# OB1_sensor_manufactured.net
KiCad netlist of a schematic drawn in EAGLE
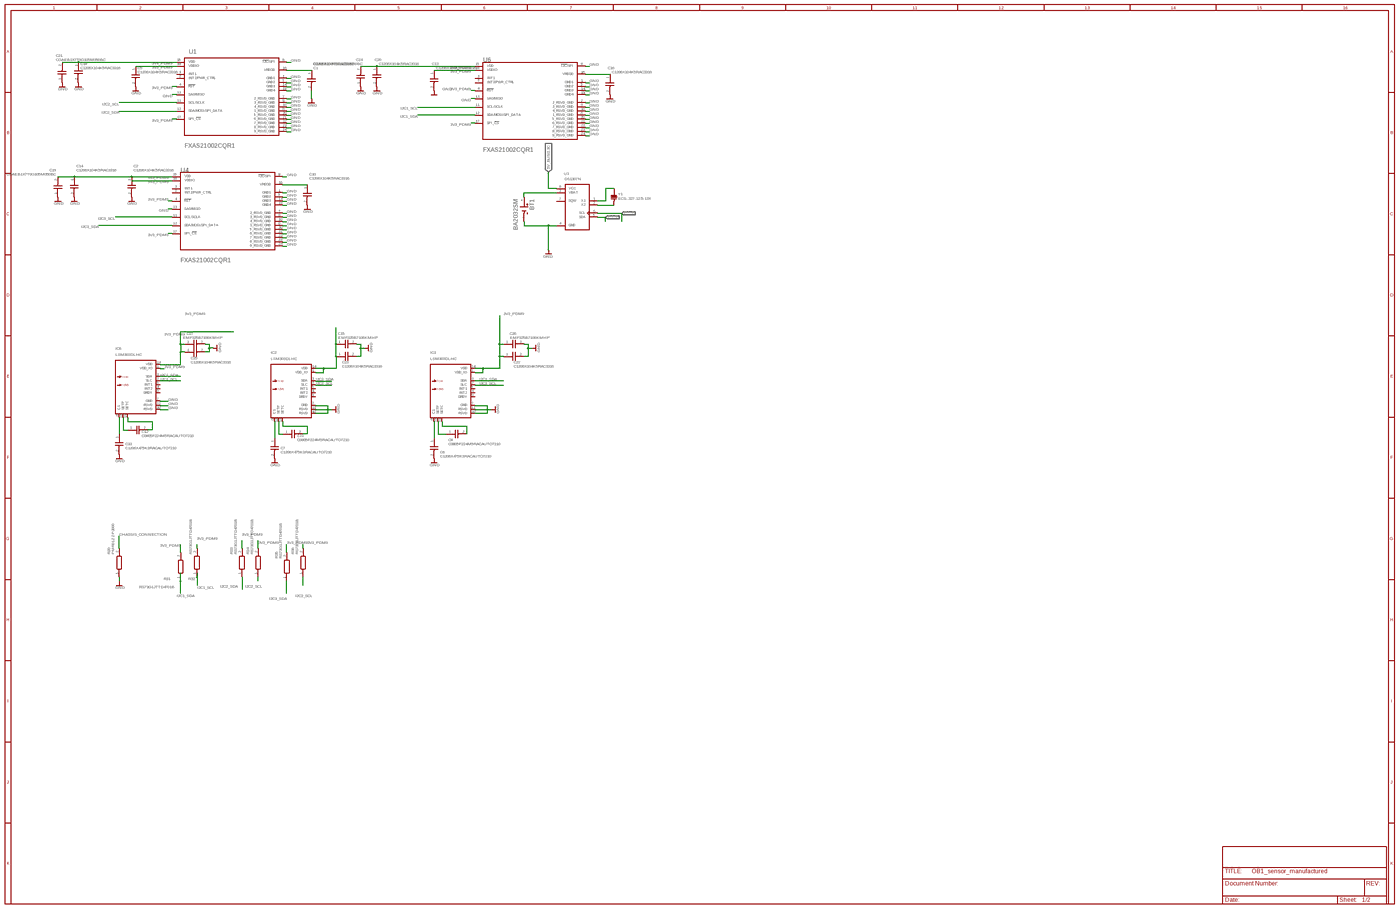
[diagram p0: schematic, sheet 1, overview]
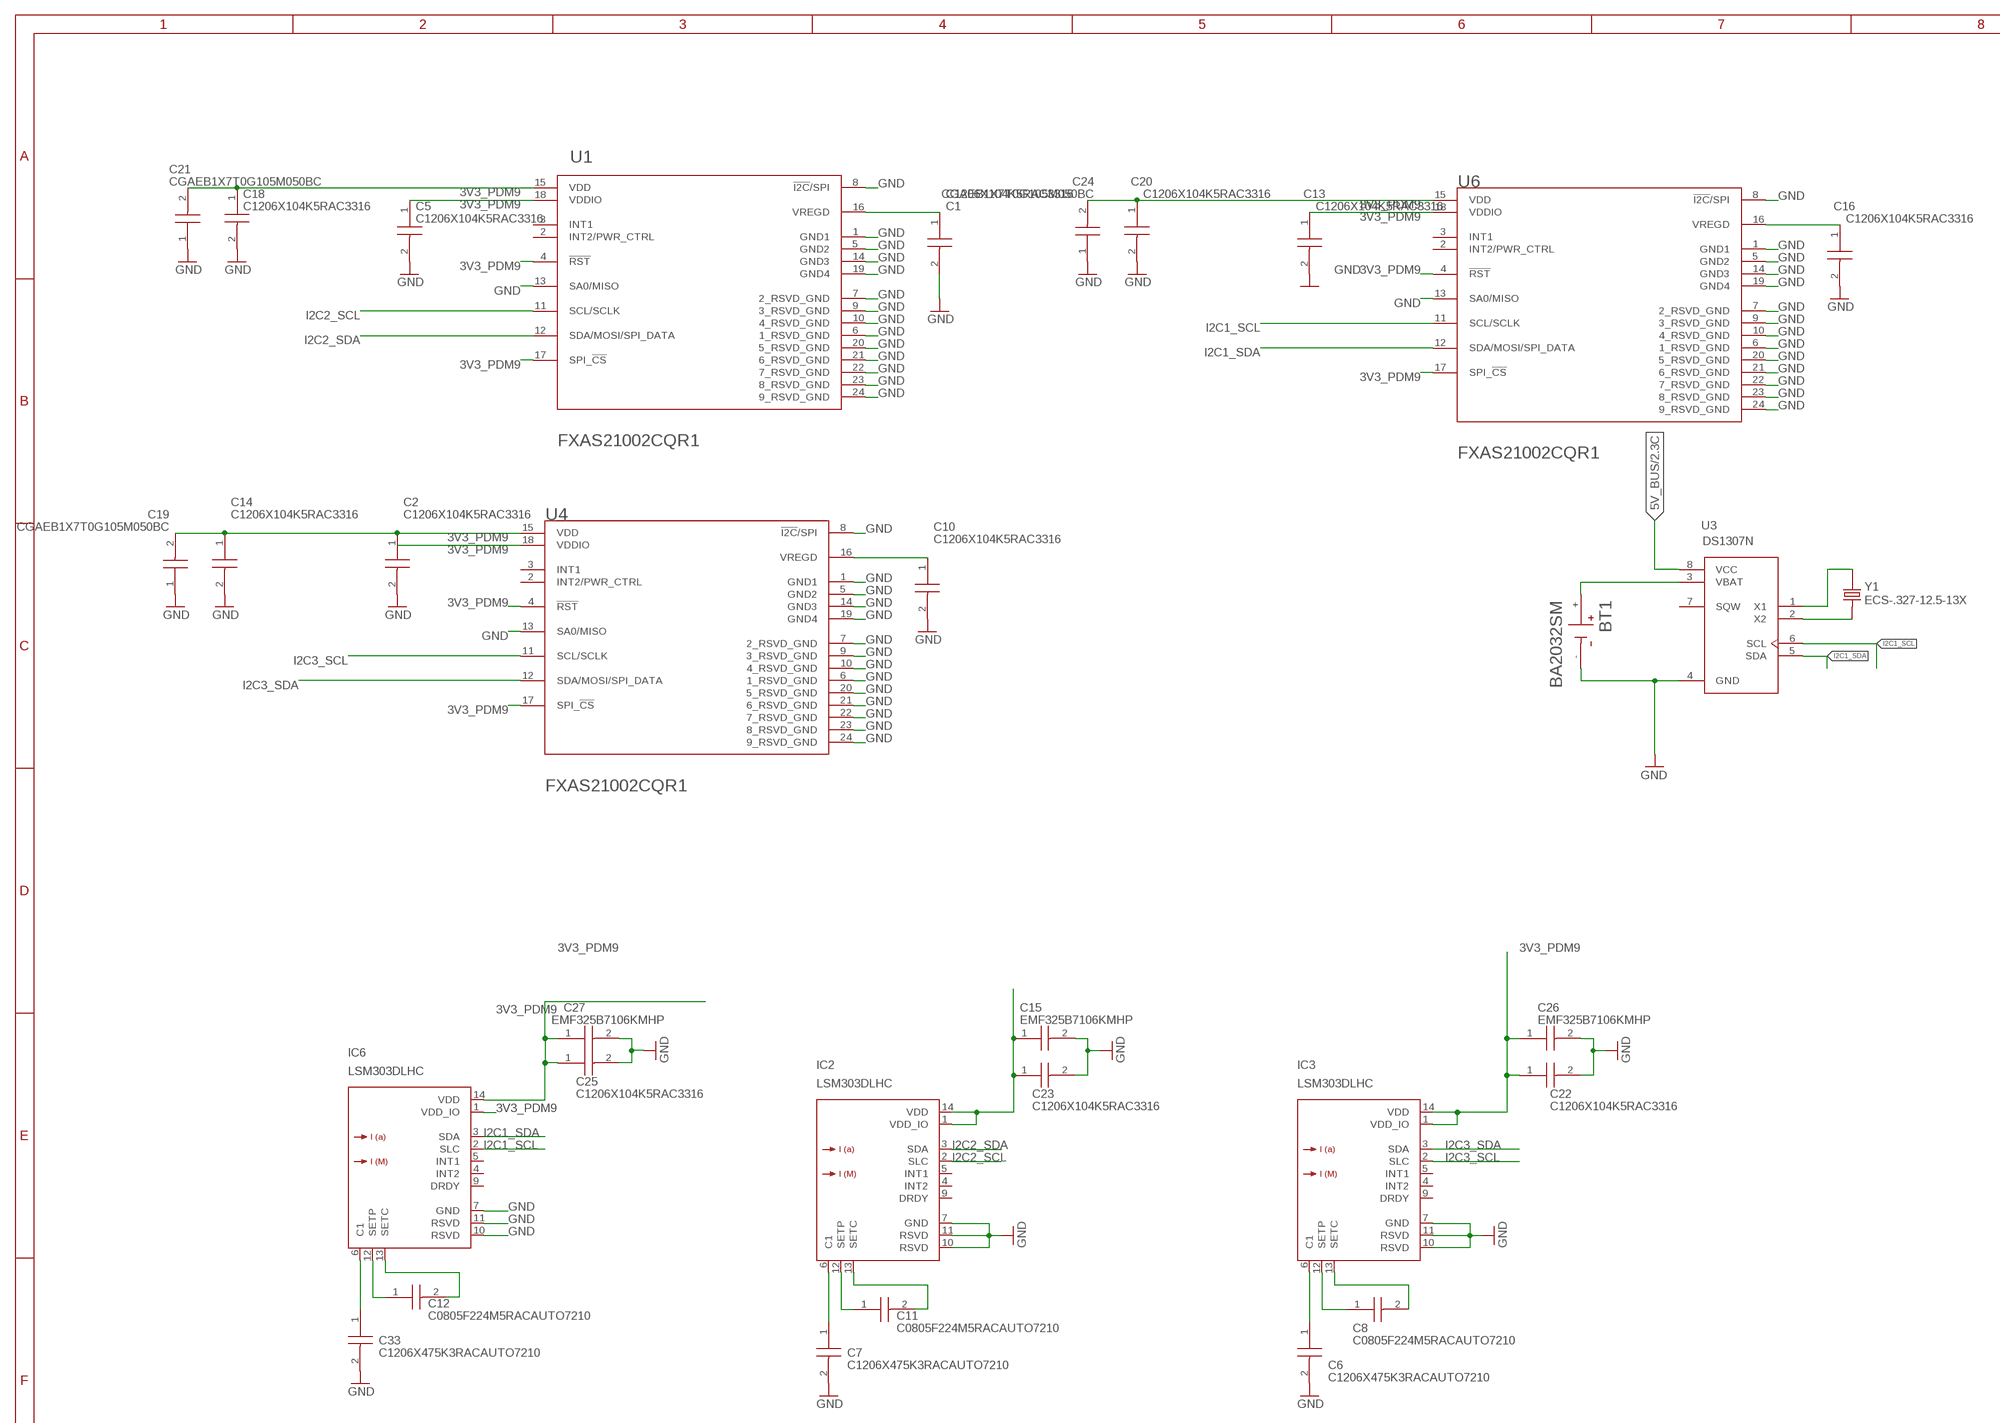
[diagram p1: schematic, sheet 1, part 1 of 4]
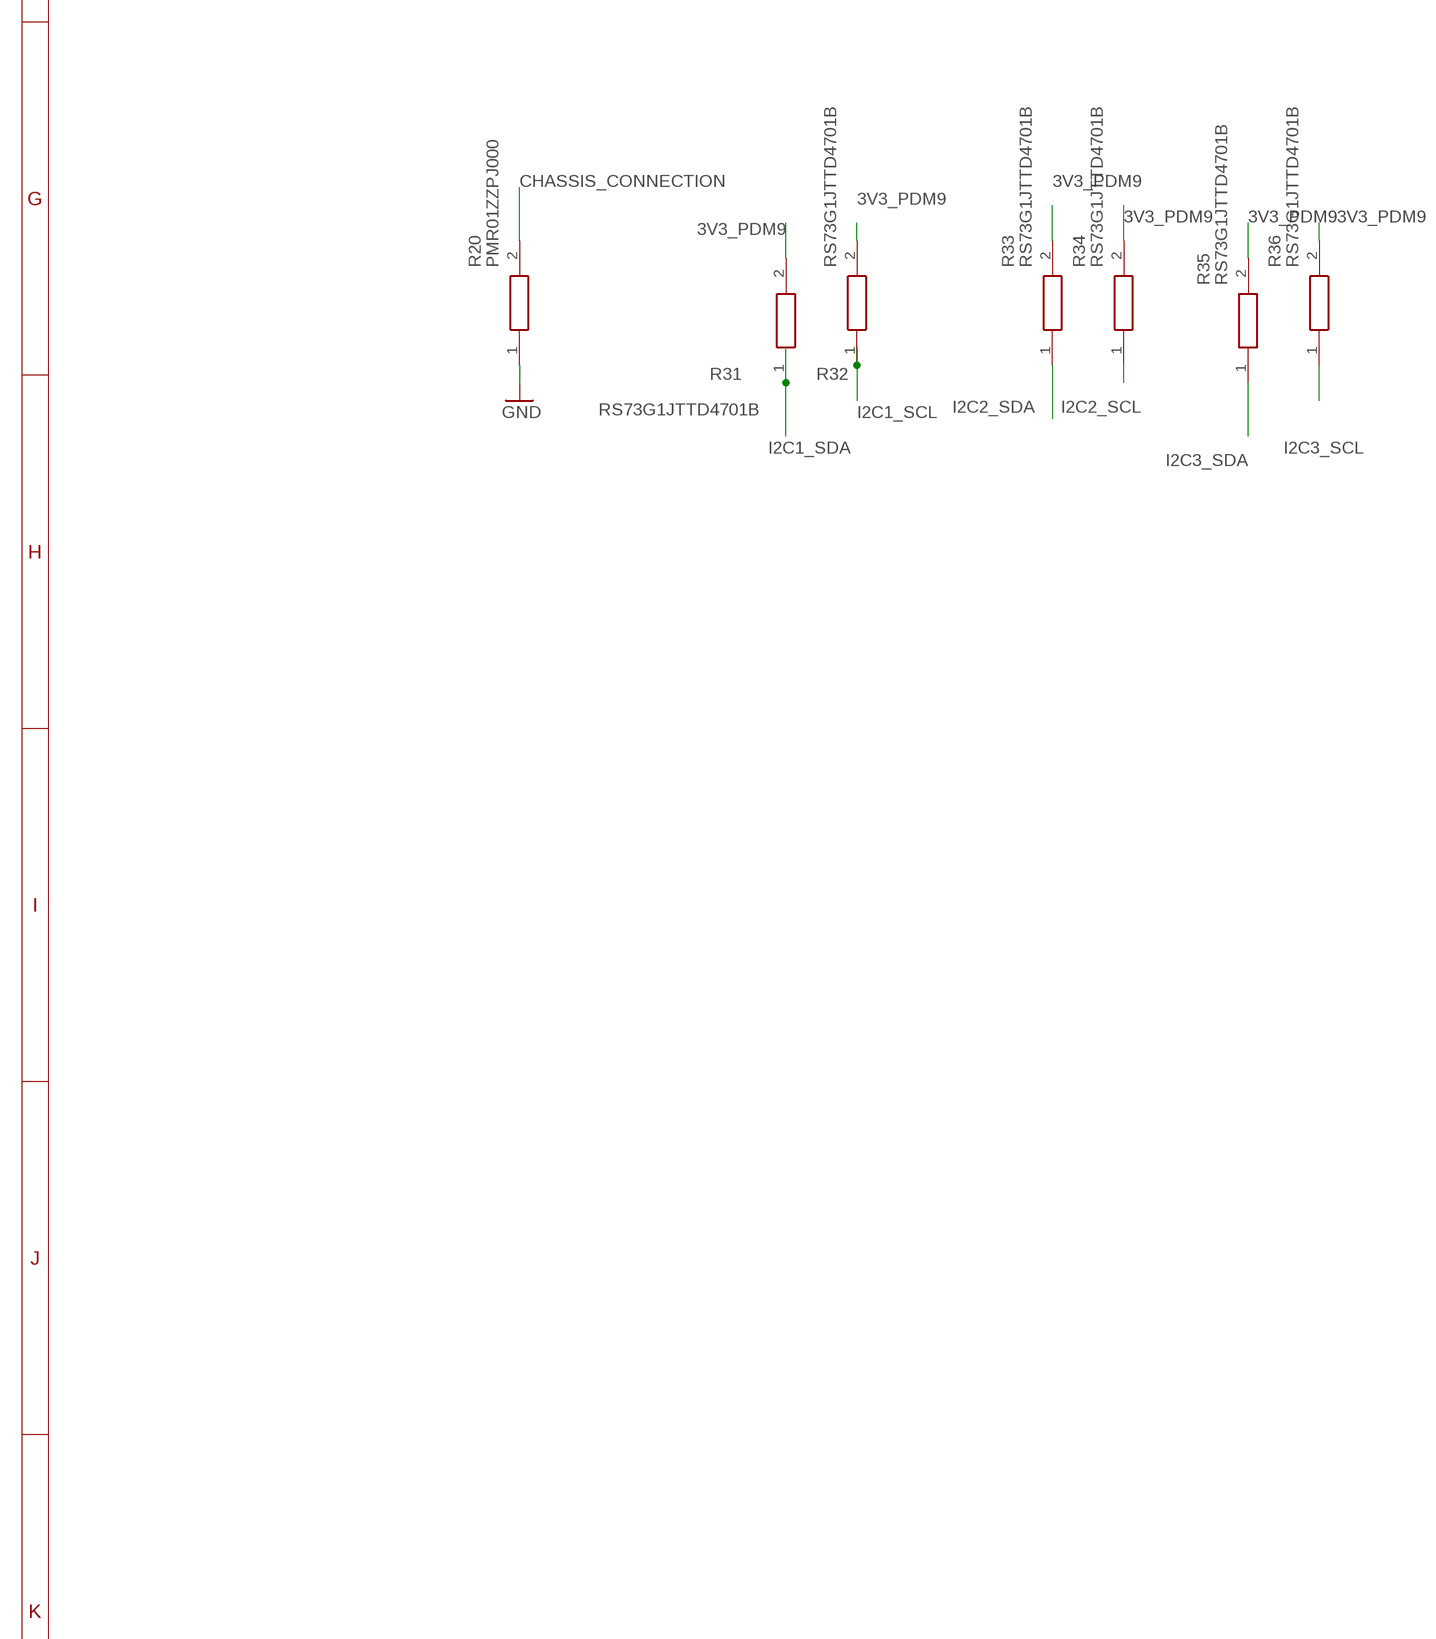
[diagram p2: schematic, sheet 1, part 2 of 4]
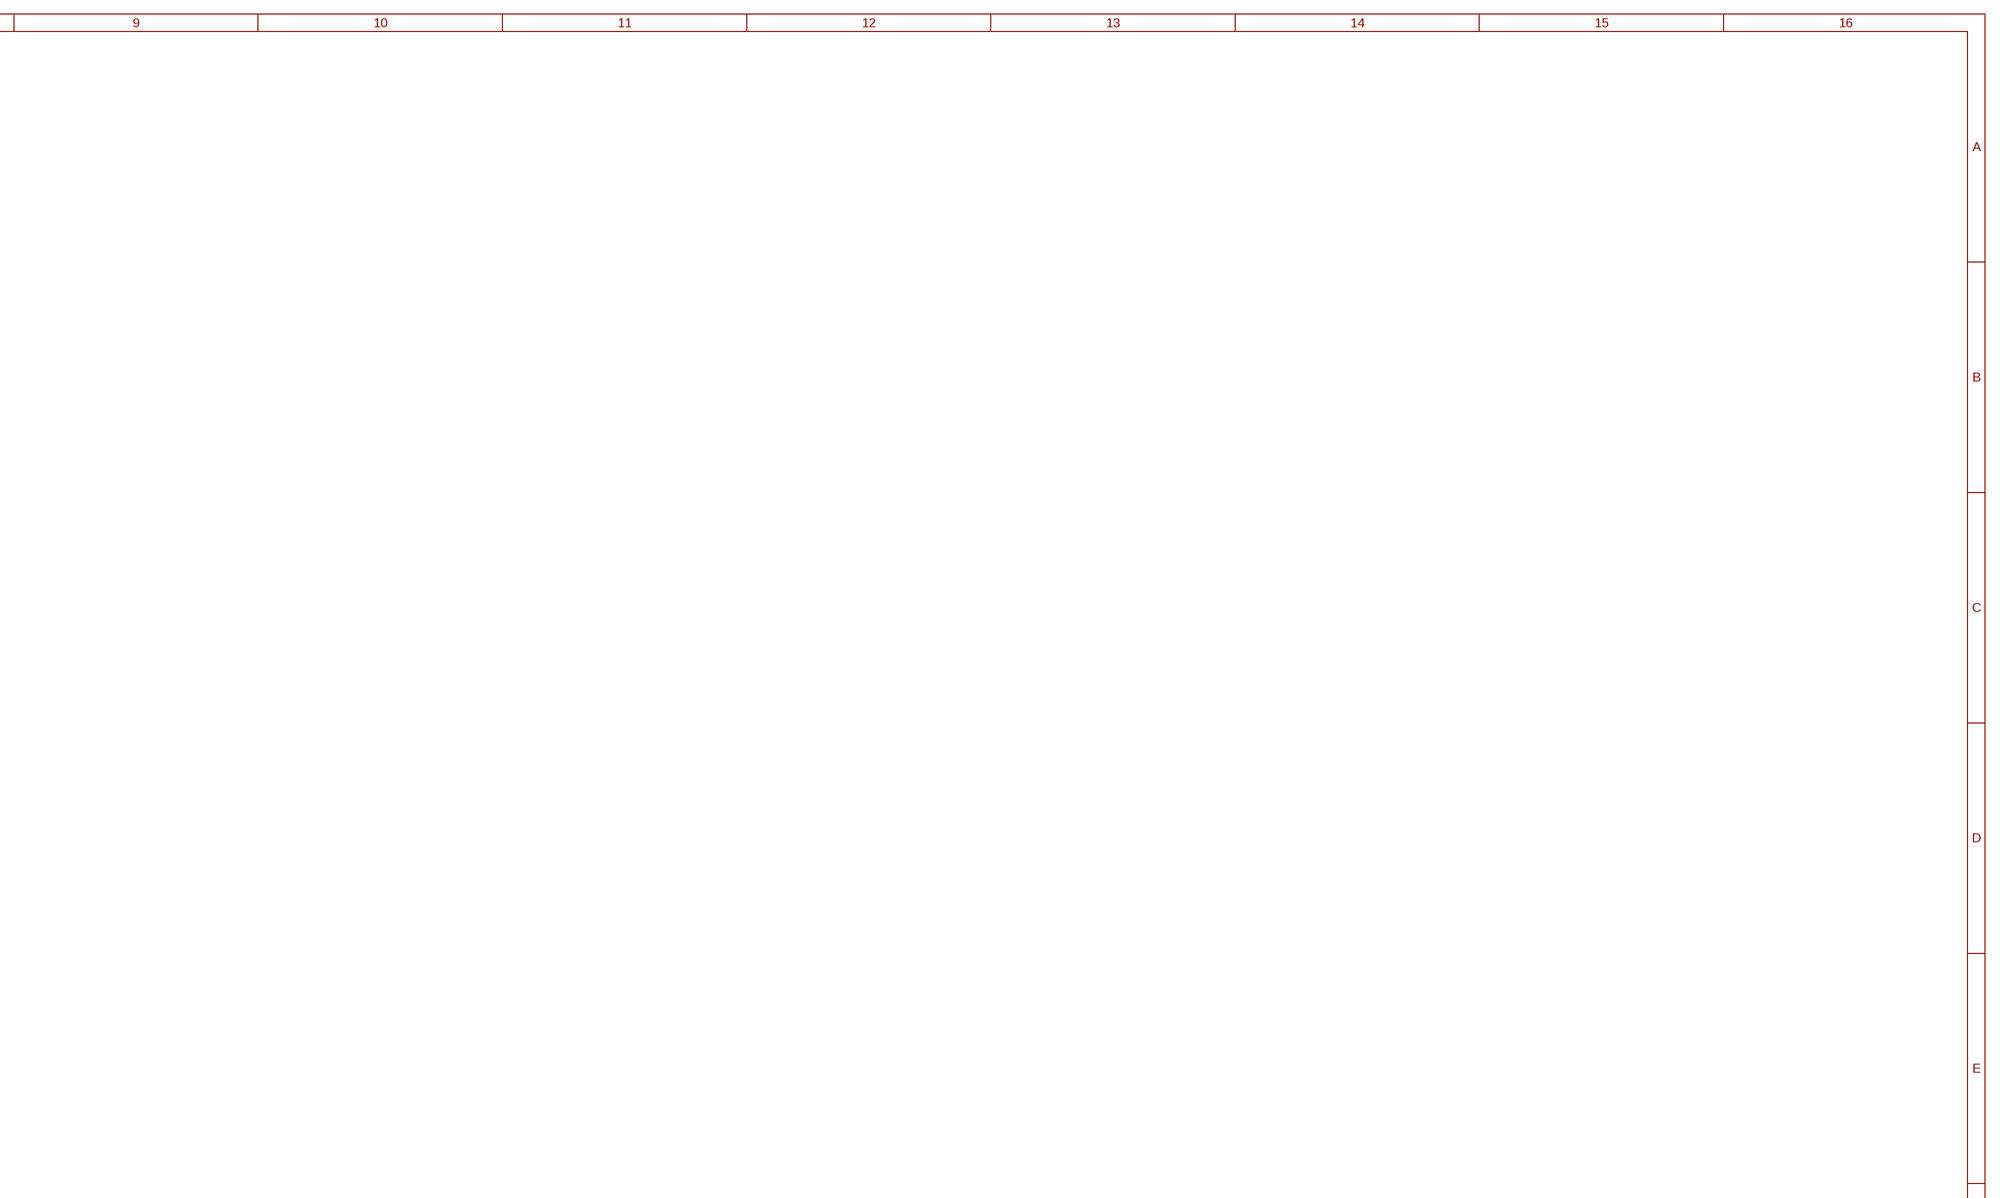
[diagram p3: schematic, sheet 1, part 3 of 4]
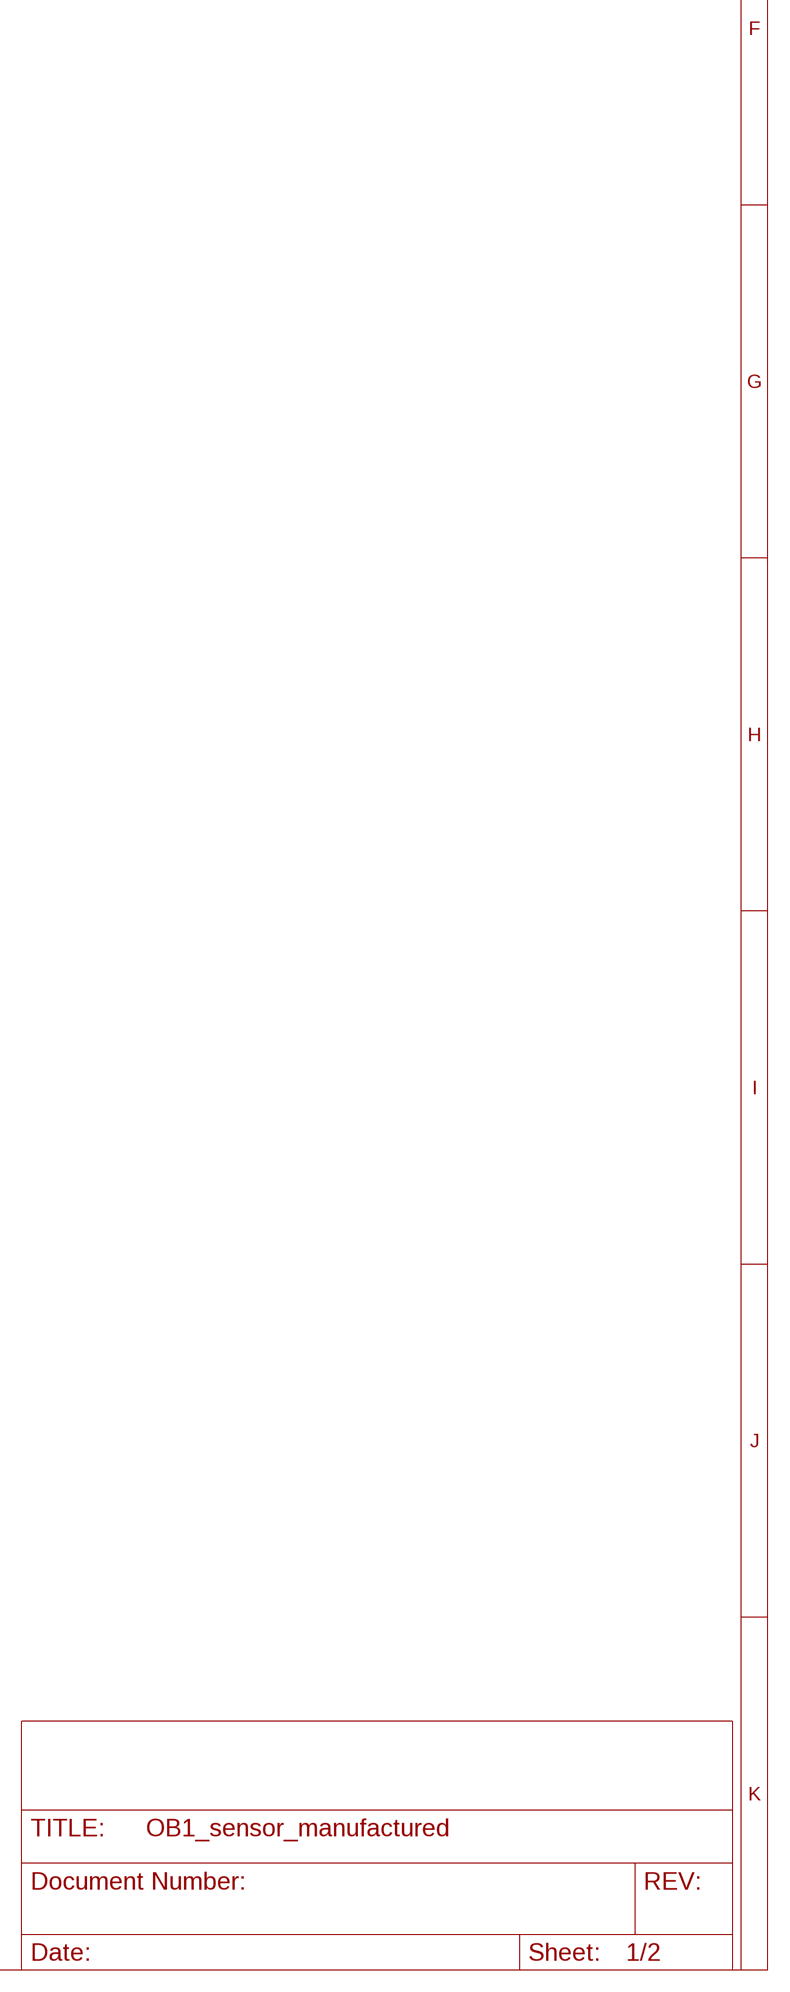
[diagram p4: schematic, sheet 1, part 4 of 4]
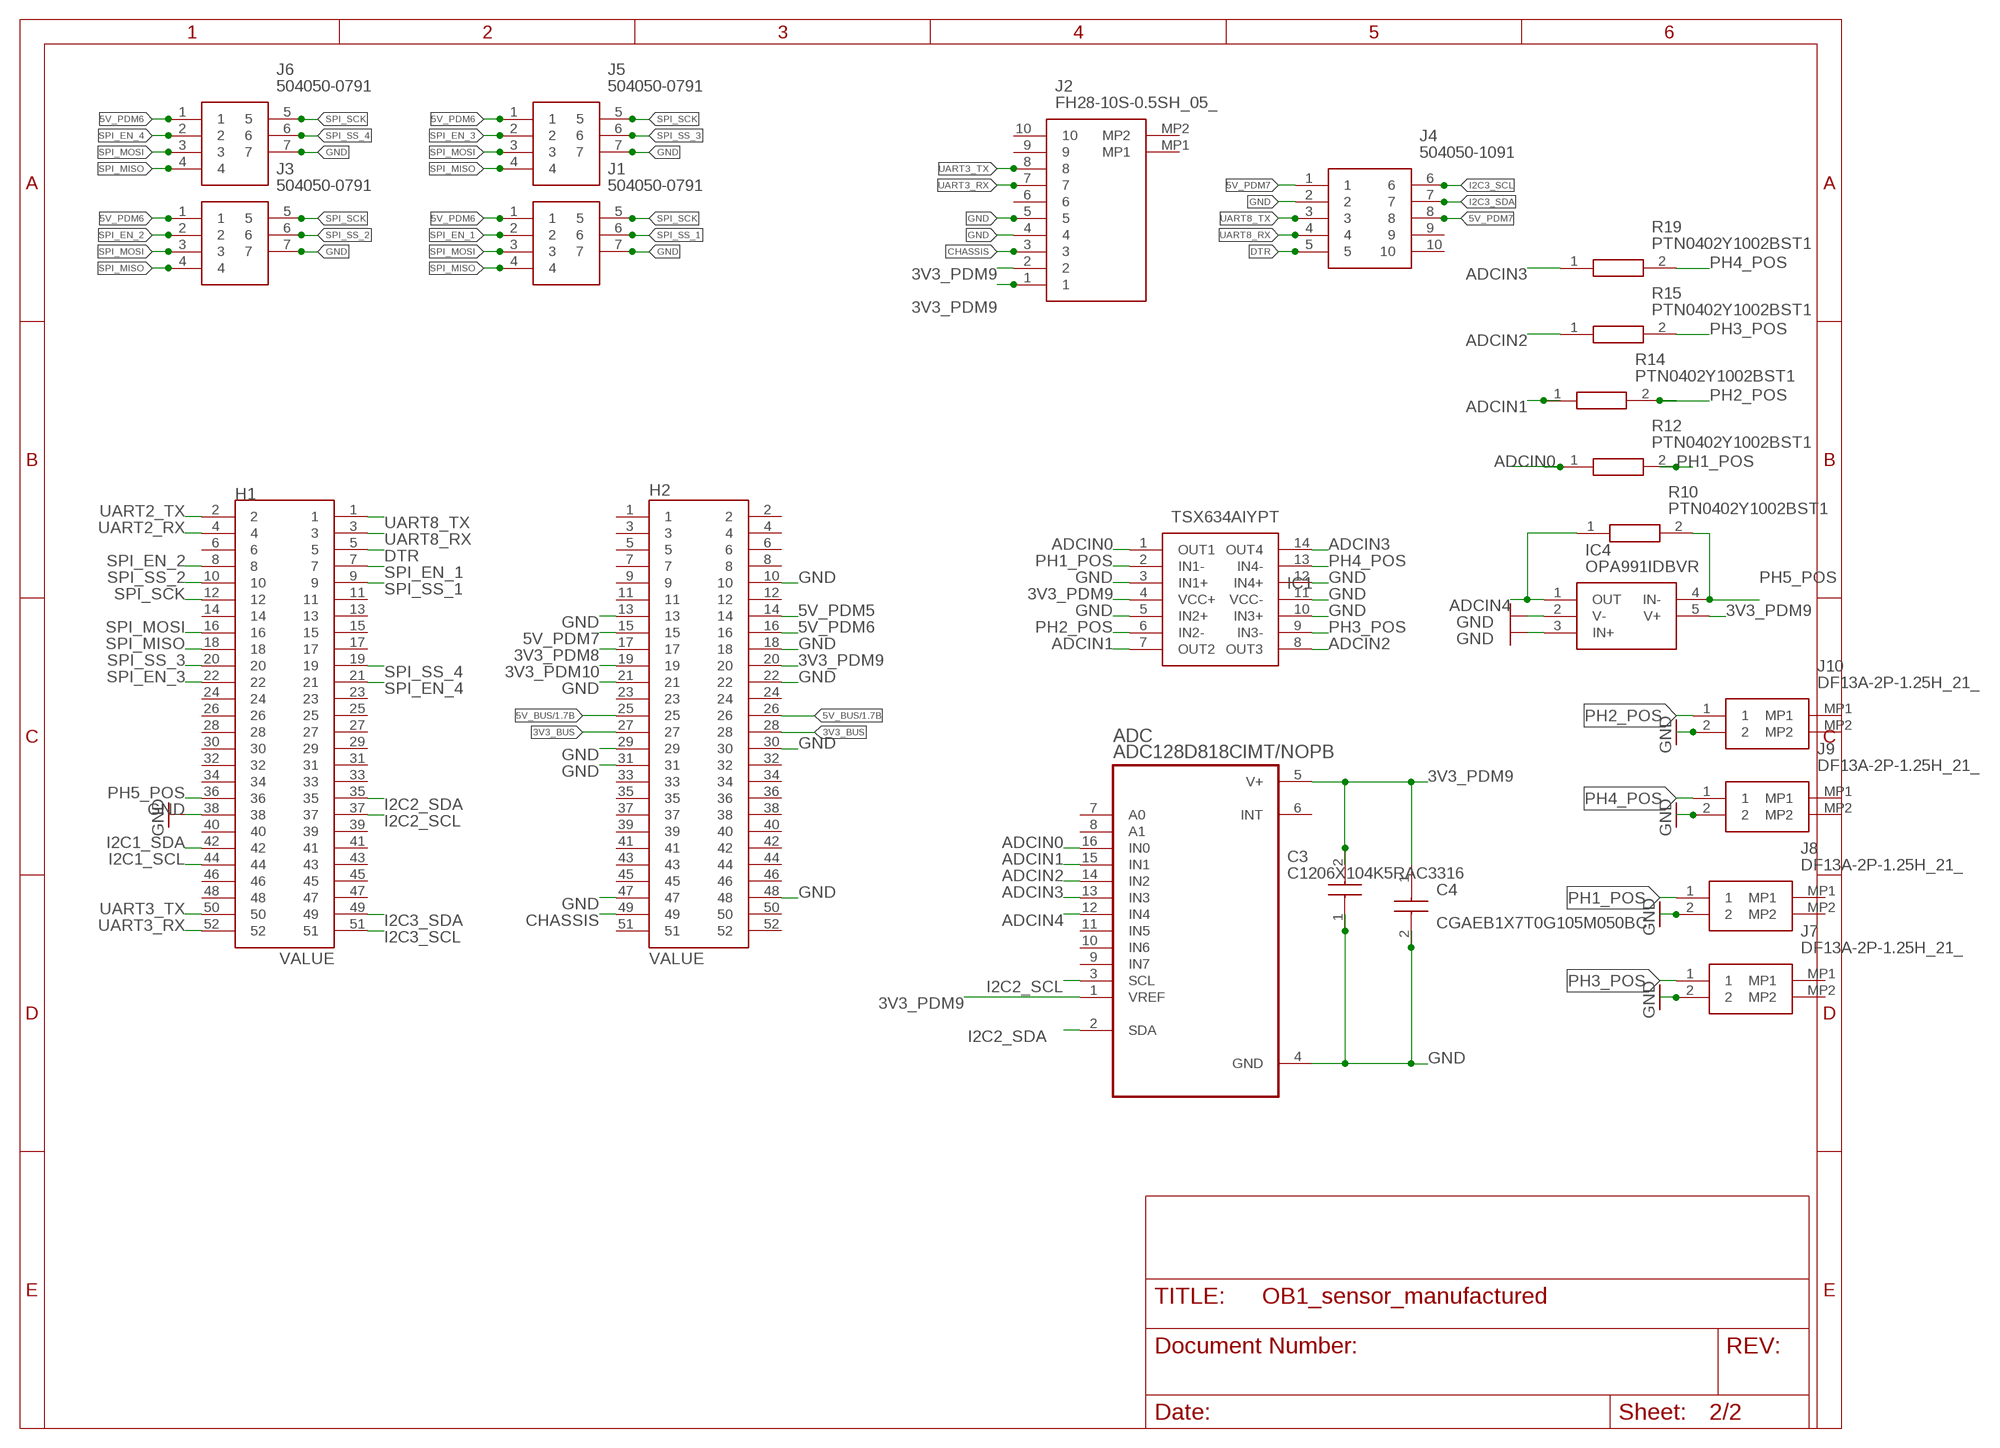
[diagram p5: schematic, sheet 2]

(export (version "E")
  (design (tool "Eeschema 10.0.6"))
  (components
    (comp (ref "BT1")
      (value "BA2032SM")
      (footprint "eagle-import:BAT_BA2032SM")
      (fields (field (name "DIGI-KEY_PART_NUMBER") "BA2032SM-ND") (field (name "MF") "MPD"))
      (libsource (lib "eagle-import") (part "BA2032SM"))
    )
    (comp (ref "C1")
      (value "C1206X104K5RAC3316")
      (footprint "eagle-import:CAPC3316X98N")
      (fields (field (name "MOUSER_PART_NUMBER") "80-C1206X104K5RC3316"))
      (libsource (lib "eagle-import") (part "C1206X104K5RAC3316"))
    )
    (comp (ref "C2")
      (value "C1206X104K5RAC3316")
      (footprint "eagle-import:CAPC3316X98N")
      (fields (field (name "MOUSER_PART_NUMBER") "80-C1206X104K5RC3316"))
      (libsource (lib "eagle-import") (part "C1206X104K5RAC3316"))
    )
    (comp (ref "C5")
      (value "C1206X104K5RAC3316")
      (footprint "eagle-import:CAPC3316X98N")
      (fields (field (name "MOUSER_PART_NUMBER") "80-C1206X104K5RC3316"))
      (libsource (lib "eagle-import") (part "C1206X104K5RAC3316"))
    )
    (comp (ref "C6")
      (value "C1206X475K3RACAUTO7210")
      (footprint "eagle-import:CAPC3316X195N")
      (fields (field (name "MOUSER_PART_NUMBER") "80-C1206X475K3RAUTLR"))
      (libsource (lib "eagle-import") (part "C1206X475K3RACAUTO7210"))
    )
    (comp (ref "C7")
      (value "C1206X475K3RACAUTO7210")
      (footprint "eagle-import:CAPC3316X195N")
      (fields (field (name "MOUSER_PART_NUMBER") "80-C1206X475K3RAUTLR"))
      (libsource (lib "eagle-import") (part "C1206X475K3RACAUTO7210"))
    )
    (comp (ref "C8")
      (value "C0805F224M5RACAUTO7210")
      (footprint "eagle-import:CAPC2012X140N")
      (fields (field (name "MOUSER_PART_NUMBER") "80-C0805F224M5RAUTLR"))
      (libsource (lib "eagle-import") (part "C0805F224M5RACAUTO7210"))
    )
    (comp (ref "C10")
      (value "C1206X104K5RAC3316")
      (footprint "eagle-import:CAPC3316X98N")
      (fields (field (name "MOUSER_PART_NUMBER") "80-C1206X104K5RC3316"))
      (libsource (lib "eagle-import") (part "C1206X104K5RAC3316"))
    )
    (comp (ref "C11")
      (value "C0805F224M5RACAUTO7210")
      (footprint "eagle-import:CAPC2012X140N")
      (fields (field (name "MOUSER_PART_NUMBER") "80-C0805F224M5RAUTLR"))
      (libsource (lib "eagle-import") (part "C0805F224M5RACAUTO7210"))
    )
    (comp (ref "C12")
      (value "C0805F224M5RACAUTO7210")
      (footprint "eagle-import:CAPC2012X140N")
      (fields (field (name "MOUSER_PART_NUMBER") "80-C0805F224M5RAUTLR"))
      (libsource (lib "eagle-import") (part "C0805F224M5RACAUTO7210"))
    )
    (comp (ref "C13")
      (value "C1206X104K5RAC3316")
      (footprint "eagle-import:CAPC3316X98N")
      (fields (field (name "MOUSER_PART_NUMBER") "80-C1206X104K5RC3316"))
      (libsource (lib "eagle-import") (part "C1206X104K5RAC3316"))
    )
    (comp (ref "C14")
      (value "C1206X104K5RAC3316")
      (footprint "eagle-import:CAPC3316X98N")
      (fields (field (name "MOUSER_PART_NUMBER") "80-C1206X104K5RC3316"))
      (libsource (lib "eagle-import") (part "C1206X104K5RAC3316"))
    )
    (comp (ref "C15")
      (value "EMF325B7106KMHP")
      (footprint "eagle-import:CAPC3225X270N")
      (fields (field (name "MOUSER_PART_NUMBER") "963-EMF325B7106KMHP"))
      (libsource (lib "eagle-import") (part "EMF325B7106KMHP"))
    )
    (comp (ref "C16")
      (value "C1206X104K5RAC3316")
      (footprint "eagle-import:CAPC3316X98N")
      (fields (field (name "MOUSER_PART_NUMBER") "80-C1206X104K5RC3316"))
      (libsource (lib "eagle-import") (part "C1206X104K5RAC3316"))
    )
    (comp (ref "C18")
      (value "C1206X104K5RAC3316")
      (footprint "eagle-import:CAPC3316X98N")
      (fields (field (name "MOUSER_PART_NUMBER") "80-C1206X104K5RC3316"))
      (libsource (lib "eagle-import") (part "C1206X104K5RAC3316"))
    )
    (comp (ref "C19")
      (value "CGAEB1X7T0G105M050BC")
      (footprint "eagle-import:CAPC0611X68N")
      (fields (field (name "MOUSER_PART_NUMBER") "810-CGAEB1X7T0G105M5"))
      (libsource (lib "eagle-import") (part "CGAEB1X7T0G105M050BC"))
    )
    (comp (ref "C20")
      (value "C1206X104K5RAC3316")
      (footprint "eagle-import:CAPC3316X98N")
      (fields (field (name "MOUSER_PART_NUMBER") "80-C1206X104K5RC3316"))
      (libsource (lib "eagle-import") (part "C1206X104K5RAC3316"))
    )
    (comp (ref "C21")
      (value "CGAEB1X7T0G105M050BC")
      (footprint "eagle-import:CAPC0611X68N")
      (fields (field (name "MOUSER_PART_NUMBER") "810-CGAEB1X7T0G105M5"))
      (libsource (lib "eagle-import") (part "CGAEB1X7T0G105M050BC"))
    )
    (comp (ref "C22")
      (value "C1206X104K5RAC3316")
      (footprint "eagle-import:CAPC3316X98N")
      (fields (field (name "MOUSER_PART_NUMBER") "80-C1206X104K5RC3316"))
      (libsource (lib "eagle-import") (part "C1206X104K5RAC3316"))
    )
    (comp (ref "C23")
      (value "C1206X104K5RAC3316")
      (footprint "eagle-import:CAPC3316X98N")
      (fields (field (name "MOUSER_PART_NUMBER") "80-C1206X104K5RC3316"))
      (libsource (lib "eagle-import") (part "C1206X104K5RAC3316"))
    )
    (comp (ref "C24")
      (value "CGAEB1X7T0G105M050BC")
      (footprint "eagle-import:CAPC0611X68N")
      (fields (field (name "MOUSER_PART_NUMBER") "810-CGAEB1X7T0G105M5"))
      (libsource (lib "eagle-import") (part "CGAEB1X7T0G105M050BC"))
    )
    (comp (ref "C25")
      (value "C1206X104K5RAC3316")
      (footprint "eagle-import:CAPC3316X98N")
      (fields (field (name "MOUSER_PART_NUMBER") "80-C1206X104K5RC3316"))
      (libsource (lib "eagle-import") (part "C1206X104K5RAC3316"))
    )
    (comp (ref "C26")
      (value "EMF325B7106KMHP")
      (footprint "eagle-import:CAPC3225X270N")
      (fields (field (name "MOUSER_PART_NUMBER") "963-EMF325B7106KMHP"))
      (libsource (lib "eagle-import") (part "EMF325B7106KMHP"))
    )
    (comp (ref "C27")
      (value "EMF325B7106KMHP")
      (footprint "eagle-import:CAPC3225X270N")
      (fields (field (name "MOUSER_PART_NUMBER") "963-EMF325B7106KMHP"))
      (libsource (lib "eagle-import") (part "EMF325B7106KMHP"))
    )
    (comp (ref "C33")
      (value "C1206X475K3RACAUTO7210")
      (footprint "eagle-import:CAPC3316X195N")
      (fields (field (name "MOUSER_PART_NUMBER") "80-C1206X475K3RAUTLR"))
      (libsource (lib "eagle-import") (part "C1206X475K3RACAUTO7210"))
    )
    (comp (ref "IC2")
      (value "LSM303DLHC")
      (footprint "eagle-import:LGA-14")
      (libsource (lib "eagle-import") (part "LSM303DLHC"))
    )
    (comp (ref "IC3")
      (value "LSM303DLHC")
      (footprint "eagle-import:LGA-14")
      (libsource (lib "eagle-import") (part "LSM303DLHC"))
    )
    (comp (ref "IC6")
      (value "LSM303DLHC")
      (footprint "eagle-import:LGA-14")
      (libsource (lib "eagle-import") (part "LSM303DLHC"))
    )
    (comp (ref "R20")
      (value "PMR01ZZPJ000")
      (footprint "eagle-import:RESC1005X35N")
      (fields (field (name "MOUSER_PART_NUMBER") "755-PMR01ZZPJ000"))
      (libsource (lib "eagle-import") (part "PMR01ZZPJ000"))
    )
    (comp (ref "R31")
      (value "RS73G1JTTD4701B")
      (footprint "eagle-import:RESC1608X55N")
      (fields (field (name "MOUSER_PART_NUMBER") "660-RS73G1JTTD4701B"))
      (libsource (lib "eagle-import") (part "RS73G1JTTD4701B"))
    )
    (comp (ref "R32")
      (value "RS73G1JTTD4701B")
      (footprint "eagle-import:RESC1608X55N")
      (fields (field (name "MOUSER_PART_NUMBER") "660-RS73G1JTTD4701B"))
      (libsource (lib "eagle-import") (part "RS73G1JTTD4701B"))
    )
    (comp (ref "R33")
      (value "RS73G1JTTD4701B")
      (footprint "eagle-import:RESC1608X55N")
      (fields (field (name "MOUSER_PART_NUMBER") "660-RS73G1JTTD4701B"))
      (libsource (lib "eagle-import") (part "RS73G1JTTD4701B"))
    )
    (comp (ref "R34")
      (value "RS73G1JTTD4701B")
      (footprint "eagle-import:RESC1608X55N")
      (fields (field (name "MOUSER_PART_NUMBER") "660-RS73G1JTTD4701B"))
      (libsource (lib "eagle-import") (part "RS73G1JTTD4701B"))
    )
    (comp (ref "R35")
      (value "RS73G1JTTD4701B")
      (footprint "eagle-import:RESC1608X55N")
      (fields (field (name "MOUSER_PART_NUMBER") "660-RS73G1JTTD4701B"))
      (libsource (lib "eagle-import") (part "RS73G1JTTD4701B"))
    )
    (comp (ref "R36")
      (value "RS73G1JTTD4701B")
      (footprint "eagle-import:RESC1608X55N")
      (fields (field (name "MOUSER_PART_NUMBER") "660-RS73G1JTTD4701B"))
      (libsource (lib "eagle-import") (part "RS73G1JTTD4701B"))
    )
    (comp (ref "U1")
      (value "NXP_FXAS21002CQR1_EDITEDNXP_FXAS21002CQR1_0_0")
      (footprint "eagle-import:NXP_FXAS21002CQR1_0_EDITED")
      (fields
        (field (name "DIGIKEY_PART_NUMBER") "FXAS21002CQR1CT-ND")
        (field (name "MF") "NXP")
        (field (name "MOUSER_PART_NUMBER") "841-FXAS21002CQR1")
      )
      (libsource (lib "eagle-import") (part "NXP_FXAS21002CQR1_EDITEDNXP_FXAS21002CQR1_0_0"))
    )
    (comp (ref "U3")
      (value "DS1307N")
      (footprint "eagle-import:DIP762W47P254L991H457Q8")
      (fields
        (field (name "DIGI-KEY_PART_NUMBER") "DS1307N+-ND")
        (field (name "MF") "Maxim Integrated")
        (field (name "MP") "DS1307N+")
      )
      (libsource (lib "eagle-import") (part "DS1307N"))
    )
    (comp (ref "U4")
      (value "NXP_FXAS21002CQR1_EDITEDNXP_FXAS21002CQR1_0_0")
      (footprint "eagle-import:NXP_FXAS21002CQR1_0_EDITED")
      (fields
        (field (name "DIGIKEY_PART_NUMBER") "FXAS21002CQR1CT-ND")
        (field (name "MF") "NXP")
        (field (name "MOUSER_PART_NUMBER") "841-FXAS21002CQR1")
      )
      (libsource (lib "eagle-import") (part "NXP_FXAS21002CQR1_EDITEDNXP_FXAS21002CQR1_0_0"))
    )
    (comp (ref "U6")
      (value "NXP_FXAS21002CQR1_EDITEDNXP_FXAS21002CQR1_0_0")
      (footprint "eagle-import:NXP_FXAS21002CQR1_0_EDITED")
      (fields
        (field (name "DIGIKEY_PART_NUMBER") "FXAS21002CQR1CT-ND")
        (field (name "MF") "NXP")
        (field (name "MOUSER_PART_NUMBER") "841-FXAS21002CQR1")
      )
      (libsource (lib "eagle-import") (part "NXP_FXAS21002CQR1_EDITEDNXP_FXAS21002CQR1_0_0"))
    )
    (comp (ref "Y1")
      (value "ECS-.327-12.5-13X")
      (footprint "eagle-import:XTAL_ECS-.327-12.5-13X")
      (fields (field (name "DIGI-KEY_PART_NUMBER") "X1124-ND") (field (name "MF") "ECS Inc."))
      (libsource (lib "eagle-import") (part "ECS-.327-12.5-13X"))
    )
    (comp (ref "ADC")
      (value "ADC128D818CIMT/NOPB")
      (footprint "eagle-import:SOP65P640X120-16N")
      (fields
        (field (name "DIGI-KEY_PART_NUMBER") "ADC128D818CIMT/NOPB-ND")
        (field (name "MF") "Texas Instruments")
      )
      (libsource (lib "eagle-import") (part "ADC128D818CIMT/NOPB"))
    )
    (comp (ref "C3")
      (value "C1206X104K5RAC3316")
      (footprint "eagle-import:CAPC3316X98N")
      (fields (field (name "MOUSER_PART_NUMBER") "80-C1206X104K5RC3316"))
      (libsource (lib "eagle-import") (part "C1206X104K5RAC3316"))
    )
    (comp (ref "C4")
      (value "CGAEB1X7T0G105M050BC")
      (footprint "eagle-import:CAPC0611X68N")
      (fields (field (name "MOUSER_PART_NUMBER") "810-CGAEB1X7T0G105M5"))
      (libsource (lib "eagle-import") (part "CGAEB1X7T0G105M050BC"))
    )
    (comp (ref "H1")
      (value "ESQ-126-39-G-D")
      (footprint "eagle-import:SAMTEC_ESQ-126-39-G-D")
      (fields (field (name "DIGI-KEY_PART_NUMBER") "SAM10462-ND") (field (name "MF") "Samtec"))
      (libsource (lib "eagle-import") (part "ESQ-126-39-G-D"))
    )
    (comp (ref "H2")
      (value "ESQ-126-39-G-D")
      (footprint "eagle-import:SAMTEC_ESQ-126-39-G-D")
      (fields (field (name "DIGI-KEY_PART_NUMBER") "SAM10462-ND") (field (name "MF") "Samtec"))
      (libsource (lib "eagle-import") (part "ESQ-126-39-G-D"))
    )
    (comp (ref "IC1")
      (value "TSX634AIYPT")
      (footprint "eagle-import:SOP65P640X120-14N")
      (fields (field (name "MOUSER_PART_NUMBER") "511-TSX634AIYPT"))
      (libsource (lib "eagle-import") (part "TSX634AIYPT"))
    )
    (comp (ref "IC4")
      (value "OPA991IDBVR")
      (footprint "eagle-import:SOT95P280X145-5N")
      (fields (field (name "MOUSER_PART_NUMBER") "595-OPA991IDBVR"))
      (libsource (lib "eagle-import") (part "OPA991IDBVR"))
    )
    (comp (ref "J1")
      (value "504050-0791")
      (footprint "eagle-import:504050-0791")
      (fields (field (name "MOUSER_PART_NUMBER") "538-504050-0791"))
      (libsource (lib "eagle-import") (part "504050-0791"))
    )
    (comp (ref "J2")
      (value "FH28-10S-0.5SH_05_")
      (footprint "eagle-import:FH2810S05SH05")
      (fields
        (field (name "MANUFACTURER_PART_NUMBER") "FH28-10S-0.5SH(05)")
        (field (name "MOUSER_PART_NUMBER") "798-FH2810S05SH05")
      )
      (libsource (lib "eagle-import") (part "FH28-10S-0.5SH_05_"))
    )
    (comp (ref "J3")
      (value "504050-0791")
      (footprint "eagle-import:504050-0791")
      (fields (field (name "MOUSER_PART_NUMBER") "538-504050-0791"))
      (libsource (lib "eagle-import") (part "504050-0791"))
    )
    (comp (ref "J4")
      (value "504050-1091")
      (footprint "eagle-import:504050-1091")
      (fields (field (name "MOUSER_PART_NUMBER") "538-504050-1091"))
      (libsource (lib "eagle-import") (part "504050-1091"))
    )
    (comp (ref "J5")
      (value "504050-0791")
      (footprint "eagle-import:504050-0791")
      (fields (field (name "MOUSER_PART_NUMBER") "538-504050-0791"))
      (libsource (lib "eagle-import") (part "504050-0791"))
    )
    (comp (ref "J6")
      (value "504050-0791")
      (footprint "eagle-import:504050-0791")
      (fields (field (name "MOUSER_PART_NUMBER") "538-504050-0791"))
      (libsource (lib "eagle-import") (part "504050-0791"))
    )
    (comp (ref "J7")
      (value "DF13A-2P-1.25H_21_")
      (footprint "eagle-import:DF13A2P125H21")
      (fields
        (field (name "MANUFACTURER_PART_NUMBER") "DF13A-2P-1.25H(21)")
        (field (name "MOUSER_PART_NUMBER") "798-DF13A2P125H21")
      )
      (libsource (lib "eagle-import") (part "DF13A-2P-1.25H_21_"))
    )
    (comp (ref "J8")
      (value "DF13A-2P-1.25H_21_")
      (footprint "eagle-import:DF13A2P125H21")
      (fields
        (field (name "MANUFACTURER_PART_NUMBER") "DF13A-2P-1.25H(21)")
        (field (name "MOUSER_PART_NUMBER") "798-DF13A2P125H21")
      )
      (libsource (lib "eagle-import") (part "DF13A-2P-1.25H_21_"))
    )
    (comp (ref "J9")
      (value "DF13A-2P-1.25H_21_")
      (footprint "eagle-import:DF13A2P125H21")
      (fields
        (field (name "MANUFACTURER_PART_NUMBER") "DF13A-2P-1.25H(21)")
        (field (name "MOUSER_PART_NUMBER") "798-DF13A2P125H21")
      )
      (libsource (lib "eagle-import") (part "DF13A-2P-1.25H_21_"))
    )
    (comp (ref "J10")
      (value "DF13A-2P-1.25H_21_")
      (footprint "eagle-import:DF13A2P125H21")
      (fields
        (field (name "MANUFACTURER_PART_NUMBER") "DF13A-2P-1.25H(21)")
        (field (name "MOUSER_PART_NUMBER") "798-DF13A2P125H21")
      )
      (libsource (lib "eagle-import") (part "DF13A-2P-1.25H_21_"))
    )
    (comp (ref "R10")
      (value "PTN0402Y1002BST1")
      (footprint "eagle-import:RESC1106X84N")
      (fields (field (name "MOUSER_PART_NUMBER") "71-PTN0402Y1002BST1"))
      (libsource (lib "eagle-import") (part "PTN0402Y1002BST1"))
    )
    (comp (ref "R12")
      (value "PTN0402Y1002BST1")
      (footprint "eagle-import:RESC1106X84N")
      (fields (field (name "MOUSER_PART_NUMBER") "71-PTN0402Y1002BST1"))
      (libsource (lib "eagle-import") (part "PTN0402Y1002BST1"))
    )
    (comp (ref "R14")
      (value "PTN0402Y1002BST1")
      (footprint "eagle-import:RESC1106X84N")
      (fields (field (name "MOUSER_PART_NUMBER") "71-PTN0402Y1002BST1"))
      (libsource (lib "eagle-import") (part "PTN0402Y1002BST1"))
    )
    (comp (ref "R15")
      (value "PTN0402Y1002BST1")
      (footprint "eagle-import:RESC1106X84N")
      (fields (field (name "MOUSER_PART_NUMBER") "71-PTN0402Y1002BST1"))
      (libsource (lib "eagle-import") (part "PTN0402Y1002BST1"))
    )
    (comp (ref "R19")
      (value "PTN0402Y1002BST1")
      (footprint "eagle-import:RESC1106X84N")
      (fields (field (name "MOUSER_PART_NUMBER") "71-PTN0402Y1002BST1"))
      (libsource (lib "eagle-import") (part "PTN0402Y1002BST1"))
    )
  )
  (nets
    (net (code "1") (name "3V3_BUS") (class "Default")
      (node (ref "H2") (pin "27") (pinfunction "27_27") (pintype "passive"))
      (node (ref "H2") (pin "28") (pinfunction "28_28") (pintype "passive"))
    )
    (net (code "2") (name "3V3_PDM8") (class "Default")
      (node (ref "H2") (pin "17") (pinfunction "17_17") (pintype "passive"))
    )
    (net (code "3") (name "3V3_PDM9") (class "Default")
      (node (ref "ADC") (pin "1") (pinfunction "VREF_1") (pintype "input"))
      (node (ref "ADC") (pin "5") (pinfunction "V+_5") (pintype "power_in"))
      (node (ref "C13") (pin "1") (pinfunction "1_1") (pintype "bidirectional"))
      (node (ref "C14") (pin "1") (pinfunction "1_1") (pintype "bidirectional"))
      (node (ref "C15") (pin "1") (pinfunction "1_1") (pintype "bidirectional"))
      (node (ref "C18") (pin "1") (pinfunction "1_1") (pintype "bidirectional"))
      (node (ref "C19") (pin "2") (pinfunction "2_2") (pintype "bidirectional"))
      (node (ref "C2") (pin "1") (pinfunction "1_1") (pintype "bidirectional"))
      (node (ref "C20") (pin "1") (pinfunction "1_1") (pintype "bidirectional"))
      (node (ref "C21") (pin "2") (pinfunction "2_2") (pintype "bidirectional"))
      (node (ref "C22") (pin "1") (pinfunction "1_1") (pintype "bidirectional"))
      (node (ref "C23") (pin "1") (pinfunction "1_1") (pintype "bidirectional"))
      (node (ref "C24") (pin "2") (pinfunction "2_2") (pintype "bidirectional"))
      (node (ref "C25") (pin "1") (pinfunction "1_1") (pintype "bidirectional"))
      (node (ref "C26") (pin "1") (pinfunction "1_1") (pintype "bidirectional"))
      (node (ref "C27") (pin "1") (pinfunction "1_1") (pintype "bidirectional"))
      (node (ref "C3") (pin "2") (pinfunction "2_2") (pintype "bidirectional"))
      (node (ref "C4") (pin "1") (pinfunction "1_1") (pintype "bidirectional"))
      (node (ref "C5") (pin "1") (pinfunction "1_1") (pintype "bidirectional"))
      (node (ref "H2") (pin "20") (pinfunction "20_20") (pintype "passive"))
      (node (ref "IC1") (pin "4") (pinfunction "VCC+_4") (pintype "bidirectional"))
      (node (ref "IC2") (pin "1") (pinfunction "VDD_IO_1") (pintype "power_in"))
      (node (ref "IC2") (pin "14") (pinfunction "VDD_14") (pintype "power_in"))
      (node (ref "IC3") (pin "1") (pinfunction "VDD_IO_1") (pintype "power_in"))
      (node (ref "IC3") (pin "14") (pinfunction "VDD_14") (pintype "power_in"))
      (node (ref "IC4") (pin "5") (pinfunction "V+_5") (pintype "bidirectional"))
      (node (ref "IC6") (pin "1") (pinfunction "VDD_IO_1") (pintype "power_in"))
      (node (ref "IC6") (pin "14") (pinfunction "VDD_14") (pintype "power_in"))
      (node (ref "J2") (pin "1") (pinfunction "1_1") (pintype "bidirectional"))
      (node (ref "J2") (pin "2") (pinfunction "2_2") (pintype "bidirectional"))
      (node (ref "R31") (pin "2") (pinfunction "2_2") (pintype "bidirectional"))
      (node (ref "R32") (pin "2") (pinfunction "2_2") (pintype "bidirectional"))
      (node (ref "R33") (pin "2") (pinfunction "2_2") (pintype "bidirectional"))
      (node (ref "R34") (pin "2") (pinfunction "2_2") (pintype "bidirectional"))
      (node (ref "R35") (pin "2") (pinfunction "2_2") (pintype "bidirectional"))
      (node (ref "R36") (pin "2") (pinfunction "2_2") (pintype "bidirectional"))
      (node (ref "U1") (pin "15") (pinfunction "VDD_15") (pintype "power_in"))
      (node (ref "U1") (pin "17") (pinfunction "SPI_~{CS}_17") (pintype "bidirectional"))
      (node (ref "U1") (pin "18") (pinfunction "VDDIO_18") (pintype "power_in"))
      (node (ref "U1") (pin "4") (pinfunction "~{RST}_4") (pintype "output"))
      (node (ref "U4") (pin "15") (pinfunction "VDD_15") (pintype "power_in"))
      (node (ref "U4") (pin "17") (pinfunction "SPI_~{CS}_17") (pintype "bidirectional"))
      (node (ref "U4") (pin "18") (pinfunction "VDDIO_18") (pintype "power_in"))
      (node (ref "U4") (pin "4") (pinfunction "~{RST}_4") (pintype "output"))
      (node (ref "U6") (pin "15") (pinfunction "VDD_15") (pintype "power_in"))
      (node (ref "U6") (pin "17") (pinfunction "SPI_~{CS}_17") (pintype "bidirectional"))
      (node (ref "U6") (pin "18") (pinfunction "VDDIO_18") (pintype "power_in"))
      (node (ref "U6") (pin "4") (pinfunction "~{RST}_4") (pintype "output"))
    )
    (net (code "4") (name "3V3_PDM10") (class "Default")
      (node (ref "H2") (pin "19") (pinfunction "19_19") (pintype "passive"))
    )
    (net (code "5") (name "5V_BUS") (class "Default")
      (node (ref "H2") (pin "25") (pinfunction "25_25") (pintype "passive"))
      (node (ref "H2") (pin "26") (pinfunction "26_26") (pintype "passive"))
      (node (ref "U3") (pin "8") (pinfunction "VCC_8") (pintype "power_in"))
    )
    (net (code "6") (name "5V_PDM5") (class "Default")
      (node (ref "H2") (pin "14") (pinfunction "14_14") (pintype "passive"))
    )
    (net (code "7") (name "5V_PDM6") (class "Default")
      (node (ref "H2") (pin "16") (pinfunction "16_16") (pintype "passive"))
      (node (ref "J1") (pin "1") (pinfunction "1_1") (pintype "bidirectional"))
      (node (ref "J3") (pin "1") (pinfunction "1_1") (pintype "bidirectional"))
      (node (ref "J5") (pin "1") (pinfunction "1_1") (pintype "bidirectional"))
      (node (ref "J6") (pin "1") (pinfunction "1_1") (pintype "bidirectional"))
    )
    (net (code "8") (name "5V_PDM7") (class "Default")
      (node (ref "H2") (pin "15") (pinfunction "15_15") (pintype "passive"))
      (node (ref "J4") (pin "1") (pinfunction "1_1") (pintype "bidirectional"))
      (node (ref "J4") (pin "8") (pinfunction "8_8") (pintype "bidirectional"))
    )
    (net (code "9") (name "ADCIN0") (class "Default")
      (node (ref "ADC") (pin "16") (pinfunction "IN0_16") (pintype "input"))
      (node (ref "IC1") (pin "1") (pinfunction "OUT1_1") (pintype "bidirectional"))
      (node (ref "R12") (pin "1") (pinfunction "1_1") (pintype "bidirectional"))
    )
    (net (code "10") (name "ADCIN1") (class "Default")
      (node (ref "ADC") (pin "15") (pinfunction "IN1_15") (pintype "input"))
      (node (ref "IC1") (pin "7") (pinfunction "OUT2_7") (pintype "bidirectional"))
      (node (ref "R14") (pin "1") (pinfunction "1_1") (pintype "bidirectional"))
    )
    (net (code "11") (name "ADCIN2") (class "Default")
      (node (ref "ADC") (pin "14") (pinfunction "IN2_14") (pintype "input"))
      (node (ref "IC1") (pin "8") (pinfunction "OUT3_8") (pintype "bidirectional"))
      (node (ref "R15") (pin "1") (pinfunction "1_1") (pintype "bidirectional"))
    )
    (net (code "12") (name "ADCIN3") (class "Default")
      (node (ref "ADC") (pin "13") (pinfunction "IN3_13") (pintype "input"))
      (node (ref "IC1") (pin "14") (pinfunction "OUT4_14") (pintype "bidirectional"))
      (node (ref "R19") (pin "1") (pinfunction "1_1") (pintype "bidirectional"))
    )
    (net (code "13") (name "ADCIN4") (class "Default")
      (node (ref "ADC") (pin "12") (pinfunction "IN4_12") (pintype "input"))
      (node (ref "IC4") (pin "1") (pinfunction "OUT_1") (pintype "bidirectional"))
      (node (ref "R10") (pin "1") (pinfunction "1_1") (pintype "bidirectional"))
    )
    (net (code "14") (name "CHASSIS") (class "Default")
      (node (ref "H2") (pin "49") (pinfunction "49_49") (pintype "passive"))
      (node (ref "J2") (pin "3") (pinfunction "3_3") (pintype "bidirectional"))
    )
    (net (code "15") (name "CHASSIS_CONNECTION") (class "Default")
      (node (ref "R20") (pin "2") (pinfunction "2_2") (pintype "bidirectional"))
    )
    (net (code "16") (name "DTR") (class "Default")
      (node (ref "H1") (pin "5") (pinfunction "5_5") (pintype "passive"))
      (node (ref "J4") (pin "5") (pinfunction "5_5") (pintype "bidirectional"))
    )
    (net (code "17") (name "GND") (class "Default")
      (node (ref "ADC") (pin "4") (pinfunction "GND_4") (pintype "power_in"))
      (node (ref "BT1") (pin "-") (pinfunction "-_-") (pintype "passive"))
      (node (ref "C1") (pin "2") (pinfunction "2_2") (pintype "bidirectional"))
      (node (ref "C10") (pin "2") (pinfunction "2_2") (pintype "bidirectional"))
      (node (ref "C13") (pin "2") (pinfunction "2_2") (pintype "bidirectional"))
      (node (ref "C14") (pin "2") (pinfunction "2_2") (pintype "bidirectional"))
      (node (ref "C15") (pin "2") (pinfunction "2_2") (pintype "bidirectional"))
      (node (ref "C16") (pin "2") (pinfunction "2_2") (pintype "bidirectional"))
      (node (ref "C18") (pin "2") (pinfunction "2_2") (pintype "bidirectional"))
      (node (ref "C19") (pin "1") (pinfunction "1_1") (pintype "bidirectional"))
      (node (ref "C2") (pin "2") (pinfunction "2_2") (pintype "bidirectional"))
      (node (ref "C20") (pin "2") (pinfunction "2_2") (pintype "bidirectional"))
      (node (ref "C21") (pin "1") (pinfunction "1_1") (pintype "bidirectional"))
      (node (ref "C22") (pin "2") (pinfunction "2_2") (pintype "bidirectional"))
      (node (ref "C23") (pin "2") (pinfunction "2_2") (pintype "bidirectional"))
      (node (ref "C24") (pin "1") (pinfunction "1_1") (pintype "bidirectional"))
      (node (ref "C25") (pin "2") (pinfunction "2_2") (pintype "bidirectional"))
      (node (ref "C26") (pin "2") (pinfunction "2_2") (pintype "bidirectional"))
      (node (ref "C27") (pin "2") (pinfunction "2_2") (pintype "bidirectional"))
      (node (ref "C3") (pin "1") (pinfunction "1_1") (pintype "bidirectional"))
      (node (ref "C33") (pin "2") (pinfunction "2_2") (pintype "bidirectional"))
      (node (ref "C4") (pin "2") (pinfunction "2_2") (pintype "bidirectional"))
      (node (ref "C5") (pin "2") (pinfunction "2_2") (pintype "bidirectional"))
      (node (ref "C6") (pin "2") (pinfunction "2_2") (pintype "bidirectional"))
      (node (ref "C7") (pin "2") (pinfunction "2_2") (pintype "bidirectional"))
      (node (ref "H1") (pin "38") (pinfunction "38_38") (pintype "passive"))
      (node (ref "H2") (pin "10") (pinfunction "10_10") (pintype "passive"))
      (node (ref "H2") (pin "13") (pinfunction "13_13") (pintype "passive"))
      (node (ref "H2") (pin "18") (pinfunction "18_18") (pintype "passive"))
      (node (ref "H2") (pin "21") (pinfunction "21_21") (pintype "passive"))
      (node (ref "H2") (pin "22") (pinfunction "22_22") (pintype "passive"))
      (node (ref "H2") (pin "29") (pinfunction "29_29") (pintype "passive"))
      (node (ref "H2") (pin "30") (pinfunction "30_30") (pintype "passive"))
      (node (ref "H2") (pin "31") (pinfunction "31_31") (pintype "passive"))
      (node (ref "H2") (pin "47") (pinfunction "47_47") (pintype "passive"))
      (node (ref "H2") (pin "48") (pinfunction "48_48") (pintype "passive"))
      (node (ref "IC1") (pin "10") (pinfunction "IN3+_10") (pintype "bidirectional"))
      (node (ref "IC1") (pin "11") (pinfunction "VCC-_11") (pintype "bidirectional"))
      (node (ref "IC1") (pin "12") (pinfunction "IN4+_12") (pintype "bidirectional"))
      (node (ref "IC1") (pin "3") (pinfunction "IN1+_3") (pintype "bidirectional"))
      (node (ref "IC1") (pin "5") (pinfunction "IN2+_5") (pintype "bidirectional"))
      (node (ref "IC2") (pin "10") (pinfunction "RSVD_10") (pintype "passive"))
      (node (ref "IC2") (pin "11") (pinfunction "RSVD_11") (pintype "passive"))
      (node (ref "IC2") (pin "7") (pinfunction "GND_7") (pintype "power_in"))
      (node (ref "IC3") (pin "10") (pinfunction "RSVD_10") (pintype "passive"))
      (node (ref "IC3") (pin "11") (pinfunction "RSVD_11") (pintype "passive"))
      (node (ref "IC3") (pin "7") (pinfunction "GND_7") (pintype "power_in"))
      (node (ref "IC4") (pin "2") (pinfunction "V-_2") (pintype "bidirectional"))
      (node (ref "IC4") (pin "3") (pinfunction "IN+_3") (pintype "bidirectional"))
      (node (ref "IC6") (pin "10") (pinfunction "RSVD_10") (pintype "passive"))
      (node (ref "IC6") (pin "11") (pinfunction "RSVD_11") (pintype "passive"))
      (node (ref "IC6") (pin "7") (pinfunction "GND_7") (pintype "power_in"))
      (node (ref "J1") (pin "7") (pinfunction "7_7") (pintype "bidirectional"))
      (node (ref "J10") (pin "2") (pinfunction "2_2") (pintype "bidirectional"))
      (node (ref "J2") (pin "4") (pinfunction "4_4") (pintype "bidirectional"))
      (node (ref "J2") (pin "5") (pinfunction "5_5") (pintype "bidirectional"))
      (node (ref "J3") (pin "7") (pinfunction "7_7") (pintype "bidirectional"))
      (node (ref "J4") (pin "2") (pinfunction "2_2") (pintype "bidirectional"))
      (node (ref "J5") (pin "7") (pinfunction "7_7") (pintype "bidirectional"))
      (node (ref "J6") (pin "7") (pinfunction "7_7") (pintype "bidirectional"))
      (node (ref "J7") (pin "2") (pinfunction "2_2") (pintype "bidirectional"))
      (node (ref "J8") (pin "2") (pinfunction "2_2") (pintype "bidirectional"))
      (node (ref "J9") (pin "2") (pinfunction "2_2") (pintype "bidirectional"))
      (node (ref "R20") (pin "1") (pinfunction "1_1") (pintype "bidirectional"))
      (node (ref "U1") (pin "1") (pinfunction "GND1_1") (pintype "power_in"))
      (node (ref "U1") (pin "10") (pinfunction "4_RSVD_GND_10") (pintype "power_in"))
      (node (ref "U1") (pin "13") (pinfunction "SA0/MISO_13") (pintype "bidirectional"))
      (node (ref "U1") (pin "14") (pinfunction "GND3_14") (pintype "power_in"))
      (node (ref "U1") (pin "19") (pinfunction "GND4_19") (pintype "power_in"))
      (node (ref "U1") (pin "20") (pinfunction "5_RSVD_GND_20") (pintype "power_in"))
      (node (ref "U1") (pin "21") (pinfunction "6_RSVD_GND_21") (pintype "power_in"))
      (node (ref "U1") (pin "22") (pinfunction "7_RSVD_GND_22") (pintype "power_in"))
      (node (ref "U1") (pin "23") (pinfunction "8_RSVD_GND_23") (pintype "power_in"))
      (node (ref "U1") (pin "24") (pinfunction "9_RSVD_GND_24") (pintype "power_in"))
      (node (ref "U1") (pin "5") (pinfunction "GND2_5") (pintype "power_in"))
      (node (ref "U1") (pin "6") (pinfunction "1_RSVD_GND_6") (pintype "power_in"))
      (node (ref "U1") (pin "7") (pinfunction "2_RSVD_GND_7") (pintype "power_in"))
      (node (ref "U1") (pin "8") (pinfunction "~{I2C}/SPI_8") (pintype "bidirectional"))
      (node (ref "U1") (pin "9") (pinfunction "3_RSVD_GND_9") (pintype "power_in"))
      (node (ref "U3") (pin "4") (pinfunction "GND_4") (pintype "power_in"))
      (node (ref "U4") (pin "1") (pinfunction "GND1_1") (pintype "power_in"))
      (node (ref "U4") (pin "10") (pinfunction "4_RSVD_GND_10") (pintype "power_in"))
      (node (ref "U4") (pin "13") (pinfunction "SA0/MISO_13") (pintype "bidirectional"))
      (node (ref "U4") (pin "14") (pinfunction "GND3_14") (pintype "power_in"))
      (node (ref "U4") (pin "19") (pinfunction "GND4_19") (pintype "power_in"))
      (node (ref "U4") (pin "20") (pinfunction "5_RSVD_GND_20") (pintype "power_in"))
      (node (ref "U4") (pin "21") (pinfunction "6_RSVD_GND_21") (pintype "power_in"))
      (node (ref "U4") (pin "22") (pinfunction "7_RSVD_GND_22") (pintype "power_in"))
      (node (ref "U4") (pin "23") (pinfunction "8_RSVD_GND_23") (pintype "power_in"))
      (node (ref "U4") (pin "24") (pinfunction "9_RSVD_GND_24") (pintype "power_in"))
      (node (ref "U4") (pin "5") (pinfunction "GND2_5") (pintype "power_in"))
      (node (ref "U4") (pin "6") (pinfunction "1_RSVD_GND_6") (pintype "power_in"))
      (node (ref "U4") (pin "7") (pinfunction "2_RSVD_GND_7") (pintype "power_in"))
      (node (ref "U4") (pin "8") (pinfunction "~{I2C}/SPI_8") (pintype "bidirectional"))
      (node (ref "U4") (pin "9") (pinfunction "3_RSVD_GND_9") (pintype "power_in"))
      (node (ref "U6") (pin "1") (pinfunction "GND1_1") (pintype "power_in"))
      (node (ref "U6") (pin "10") (pinfunction "4_RSVD_GND_10") (pintype "power_in"))
      (node (ref "U6") (pin "13") (pinfunction "SA0/MISO_13") (pintype "bidirectional"))
      (node (ref "U6") (pin "14") (pinfunction "GND3_14") (pintype "power_in"))
      (node (ref "U6") (pin "19") (pinfunction "GND4_19") (pintype "power_in"))
      (node (ref "U6") (pin "20") (pinfunction "5_RSVD_GND_20") (pintype "power_in"))
      (node (ref "U6") (pin "21") (pinfunction "6_RSVD_GND_21") (pintype "power_in"))
      (node (ref "U6") (pin "22") (pinfunction "7_RSVD_GND_22") (pintype "power_in"))
      (node (ref "U6") (pin "23") (pinfunction "8_RSVD_GND_23") (pintype "power_in"))
      (node (ref "U6") (pin "24") (pinfunction "9_RSVD_GND_24") (pintype "power_in"))
      (node (ref "U6") (pin "5") (pinfunction "GND2_5") (pintype "power_in"))
      (node (ref "U6") (pin "6") (pinfunction "1_RSVD_GND_6") (pintype "power_in"))
      (node (ref "U6") (pin "7") (pinfunction "2_RSVD_GND_7") (pintype "power_in"))
      (node (ref "U6") (pin "8") (pinfunction "~{I2C}/SPI_8") (pintype "bidirectional"))
      (node (ref "U6") (pin "9") (pinfunction "3_RSVD_GND_9") (pintype "power_in"))
    )
    (net (code "18") (name "I2C1_SCL") (class "Default")
      (node (ref "H1") (pin "44") (pinfunction "44_44") (pintype "passive"))
      (node (ref "IC6") (pin "2") (pinfunction "SLC_2") (pintype "bidirectional"))
      (node (ref "R32") (pin "1") (pinfunction "1_1") (pintype "bidirectional"))
      (node (ref "U3") (pin "6") (pinfunction "SCL_6") (pintype "input"))
      (node (ref "U6") (pin "11") (pinfunction "SCL/SCLK_11") (pintype "bidirectional"))
    )
    (net (code "19") (name "I2C1_SDA") (class "Default")
      (node (ref "H1") (pin "42") (pinfunction "42_42") (pintype "passive"))
      (node (ref "IC6") (pin "3") (pinfunction "SDA_3") (pintype "bidirectional"))
      (node (ref "R31") (pin "1") (pinfunction "1_1") (pintype "bidirectional"))
      (node (ref "U3") (pin "5") (pinfunction "SDA_5") (pintype "bidirectional"))
      (node (ref "U6") (pin "12") (pinfunction "SDA/MOSI/SPI_DATA_12") (pintype "bidirectional"))
    )
    (net (code "20") (name "I2C2_SCL") (class "Default")
      (node (ref "ADC") (pin "3") (pinfunction "SCL_3") (pintype "input"))
      (node (ref "H1") (pin "37") (pinfunction "37_37") (pintype "passive"))
      (node (ref "IC2") (pin "2") (pinfunction "SLC_2") (pintype "bidirectional"))
      (node (ref "R34") (pin "1") (pinfunction "1_1") (pintype "bidirectional"))
      (node (ref "U1") (pin "11") (pinfunction "SCL/SCLK_11") (pintype "bidirectional"))
    )
    (net (code "21") (name "I2C2_SDA") (class "Default")
      (node (ref "ADC") (pin "2") (pinfunction "SDA_2") (pintype "bidirectional"))
      (node (ref "H1") (pin "35") (pinfunction "35_35") (pintype "passive"))
      (node (ref "IC2") (pin "3") (pinfunction "SDA_3") (pintype "bidirectional"))
      (node (ref "R33") (pin "1") (pinfunction "1_1") (pintype "bidirectional"))
      (node (ref "U1") (pin "12") (pinfunction "SDA/MOSI/SPI_DATA_12") (pintype "bidirectional"))
    )
    (net (code "22") (name "I2C3_SCL") (class "Default")
      (node (ref "H1") (pin "51") (pinfunction "51_51") (pintype "passive"))
      (node (ref "IC3") (pin "2") (pinfunction "SLC_2") (pintype "bidirectional"))
      (node (ref "J4") (pin "6") (pinfunction "6_6") (pintype "bidirectional"))
      (node (ref "R36") (pin "1") (pinfunction "1_1") (pintype "bidirectional"))
      (node (ref "U4") (pin "11") (pinfunction "SCL/SCLK_11") (pintype "bidirectional"))
    )
    (net (code "23") (name "I2C3_SDA") (class "Default")
      (node (ref "H1") (pin "49") (pinfunction "49_49") (pintype "passive"))
      (node (ref "IC3") (pin "3") (pinfunction "SDA_3") (pintype "bidirectional"))
      (node (ref "J4") (pin "7") (pinfunction "7_7") (pintype "bidirectional"))
      (node (ref "R35") (pin "1") (pinfunction "1_1") (pintype "bidirectional"))
      (node (ref "U4") (pin "12") (pinfunction "SDA/MOSI/SPI_DATA_12") (pintype "bidirectional"))
    )
    (net (code "24") (name "Net-(IC2-C1)") (class "Default")
      (node (ref "C7") (pin "1") (pinfunction "1_1") (pintype "bidirectional"))
      (node (ref "IC2") (pin "6") (pinfunction "C1_6") (pintype "passive"))
    )
    (net (code "25") (name "Net-(IC2-SETC)") (class "Default")
      (node (ref "C11") (pin "2") (pinfunction "2_2") (pintype "bidirectional"))
      (node (ref "IC2") (pin "13") (pinfunction "SETC_13") (pintype "passive"))
    )
    (net (code "26") (name "Net-(IC2-SETP)") (class "Default")
      (node (ref "C11") (pin "1") (pinfunction "1_1") (pintype "bidirectional"))
      (node (ref "IC2") (pin "12") (pinfunction "SETP_12") (pintype "passive"))
    )
    (net (code "27") (name "Net-(IC3-C1)") (class "Default")
      (node (ref "C6") (pin "1") (pinfunction "1_1") (pintype "bidirectional"))
      (node (ref "IC3") (pin "6") (pinfunction "C1_6") (pintype "passive"))
    )
    (net (code "28") (name "Net-(IC3-SETC)") (class "Default")
      (node (ref "C8") (pin "2") (pinfunction "2_2") (pintype "bidirectional"))
      (node (ref "IC3") (pin "13") (pinfunction "SETC_13") (pintype "passive"))
    )
    (net (code "29") (name "Net-(IC3-SETP)") (class "Default")
      (node (ref "C8") (pin "1") (pinfunction "1_1") (pintype "bidirectional"))
      (node (ref "IC3") (pin "12") (pinfunction "SETP_12") (pintype "passive"))
    )
    (net (code "30") (name "Net-(IC6-C1)") (class "Default")
      (node (ref "C33") (pin "1") (pinfunction "1_1") (pintype "bidirectional"))
      (node (ref "IC6") (pin "6") (pinfunction "C1_6") (pintype "passive"))
    )
    (net (code "31") (name "Net-(IC6-SETC)") (class "Default")
      (node (ref "C12") (pin "2") (pinfunction "2_2") (pintype "bidirectional"))
      (node (ref "IC6") (pin "13") (pinfunction "SETC_13") (pintype "passive"))
    )
    (net (code "32") (name "Net-(IC6-SETP)") (class "Default")
      (node (ref "C12") (pin "1") (pinfunction "1_1") (pintype "bidirectional"))
      (node (ref "IC6") (pin "12") (pinfunction "SETP_12") (pintype "passive"))
    )
    (net (code "33") (name "Net-(U1-VREGD)") (class "Default")
      (node (ref "C1") (pin "1") (pinfunction "1_1") (pintype "bidirectional"))
      (node (ref "U1") (pin "16") (pinfunction "VREGD_16") (pintype "output"))
    )
    (net (code "34") (name "Net-(U3-VBAT)") (class "Default")
      (node (ref "BT1") (pin "+") (pinfunction "+_+") (pintype "passive"))
      (node (ref "U3") (pin "3") (pinfunction "VBAT_3") (pintype "power_in"))
    )
    (net (code "35") (name "Net-(U3-X1)") (class "Default")
      (node (ref "U3") (pin "1") (pinfunction "X1_1") (pintype "input"))
      (node (ref "Y1") (pin "1") (pinfunction "1_1") (pintype "passive"))
    )
    (net (code "36") (name "Net-(U3-X2)") (class "Default")
      (node (ref "U3") (pin "2") (pinfunction "X2_2") (pintype "output"))
      (node (ref "Y1") (pin "2") (pinfunction "2_2") (pintype "passive"))
    )
    (net (code "37") (name "Net-(U4-VREGD)") (class "Default")
      (node (ref "C10") (pin "1") (pinfunction "1_1") (pintype "bidirectional"))
      (node (ref "U4") (pin "16") (pinfunction "VREGD_16") (pintype "output"))
    )
    (net (code "38") (name "Net-(U6-VREGD)") (class "Default")
      (node (ref "C16") (pin "1") (pinfunction "1_1") (pintype "bidirectional"))
      (node (ref "U6") (pin "16") (pinfunction "VREGD_16") (pintype "output"))
    )
    (net (code "39") (name "PH1_POS") (class "Default")
      (node (ref "IC1") (pin "2") (pinfunction "IN1-_2") (pintype "bidirectional"))
      (node (ref "J8") (pin "1") (pinfunction "1_1") (pintype "bidirectional"))
      (node (ref "R12") (pin "2") (pinfunction "2_2") (pintype "bidirectional"))
    )
    (net (code "40") (name "PH2_POS") (class "Default")
      (node (ref "IC1") (pin "6") (pinfunction "IN2-_6") (pintype "bidirectional"))
      (node (ref "J10") (pin "1") (pinfunction "1_1") (pintype "bidirectional"))
      (node (ref "R14") (pin "2") (pinfunction "2_2") (pintype "bidirectional"))
    )
    (net (code "41") (name "PH3_POS") (class "Default")
      (node (ref "IC1") (pin "9") (pinfunction "IN3-_9") (pintype "bidirectional"))
      (node (ref "J7") (pin "1") (pinfunction "1_1") (pintype "bidirectional"))
      (node (ref "R15") (pin "2") (pinfunction "2_2") (pintype "bidirectional"))
    )
    (net (code "42") (name "PH4_POS") (class "Default")
      (node (ref "IC1") (pin "13") (pinfunction "IN4-_13") (pintype "bidirectional"))
      (node (ref "J9") (pin "1") (pinfunction "1_1") (pintype "bidirectional"))
      (node (ref "R19") (pin "2") (pinfunction "2_2") (pintype "bidirectional"))
    )
    (net (code "43") (name "PH5_POS") (class "Default")
      (node (ref "H1") (pin "36") (pinfunction "36_36") (pintype "passive"))
      (node (ref "IC4") (pin "4") (pinfunction "IN-_4") (pintype "bidirectional"))
      (node (ref "R10") (pin "2") (pinfunction "2_2") (pintype "bidirectional"))
    )
    (net (code "44") (name "SPI_EN_1") (class "Default")
      (node (ref "H1") (pin "7") (pinfunction "7_7") (pintype "passive"))
      (node (ref "J1") (pin "2") (pinfunction "2_2") (pintype "bidirectional"))
    )
    (net (code "45") (name "SPI_EN_2") (class "Default")
      (node (ref "H1") (pin "8") (pinfunction "8_8") (pintype "passive"))
      (node (ref "J3") (pin "2") (pinfunction "2_2") (pintype "bidirectional"))
    )
    (net (code "46") (name "SPI_EN_3") (class "Default")
      (node (ref "H1") (pin "22") (pinfunction "22_22") (pintype "passive"))
      (node (ref "J5") (pin "2") (pinfunction "2_2") (pintype "bidirectional"))
    )
    (net (code "47") (name "SPI_EN_4") (class "Default")
      (node (ref "H1") (pin "21") (pinfunction "21_21") (pintype "passive"))
      (node (ref "J6") (pin "2") (pinfunction "2_2") (pintype "bidirectional"))
    )
    (net (code "48") (name "SPI_MISO") (class "Default")
      (node (ref "H1") (pin "18") (pinfunction "18_18") (pintype "passive"))
      (node (ref "J1") (pin "4") (pinfunction "4_4") (pintype "bidirectional"))
      (node (ref "J3") (pin "4") (pinfunction "4_4") (pintype "bidirectional"))
      (node (ref "J5") (pin "4") (pinfunction "4_4") (pintype "bidirectional"))
      (node (ref "J6") (pin "4") (pinfunction "4_4") (pintype "bidirectional"))
    )
    (net (code "49") (name "SPI_MOSI") (class "Default")
      (node (ref "H1") (pin "16") (pinfunction "16_16") (pintype "passive"))
      (node (ref "J1") (pin "3") (pinfunction "3_3") (pintype "bidirectional"))
      (node (ref "J3") (pin "3") (pinfunction "3_3") (pintype "bidirectional"))
      (node (ref "J5") (pin "3") (pinfunction "3_3") (pintype "bidirectional"))
      (node (ref "J6") (pin "3") (pinfunction "3_3") (pintype "bidirectional"))
    )
    (net (code "50") (name "SPI_SCK") (class "Default")
      (node (ref "H1") (pin "12") (pinfunction "12_12") (pintype "passive"))
      (node (ref "J1") (pin "5") (pinfunction "5_5") (pintype "bidirectional"))
      (node (ref "J3") (pin "5") (pinfunction "5_5") (pintype "bidirectional"))
      (node (ref "J5") (pin "5") (pinfunction "5_5") (pintype "bidirectional"))
      (node (ref "J6") (pin "5") (pinfunction "5_5") (pintype "bidirectional"))
    )
    (net (code "51") (name "SPI_SS_1") (class "Default")
      (node (ref "H1") (pin "9") (pinfunction "9_9") (pintype "passive"))
      (node (ref "J1") (pin "6") (pinfunction "6_6") (pintype "bidirectional"))
    )
    (net (code "52") (name "SPI_SS_2") (class "Default")
      (node (ref "H1") (pin "10") (pinfunction "10_10") (pintype "passive"))
      (node (ref "J3") (pin "6") (pinfunction "6_6") (pintype "bidirectional"))
    )
    (net (code "53") (name "SPI_SS_3") (class "Default")
      (node (ref "H1") (pin "20") (pinfunction "20_20") (pintype "passive"))
      (node (ref "J5") (pin "6") (pinfunction "6_6") (pintype "bidirectional"))
    )
    (net (code "54") (name "SPI_SS_4") (class "Default")
      (node (ref "H1") (pin "19") (pinfunction "19_19") (pintype "passive"))
      (node (ref "J6") (pin "6") (pinfunction "6_6") (pintype "bidirectional"))
    )
    (net (code "55") (name "UART2_RX") (class "Default")
      (node (ref "H1") (pin "4") (pinfunction "4_4") (pintype "passive"))
    )
    (net (code "56") (name "UART2_TX") (class "Default")
      (node (ref "H1") (pin "2") (pinfunction "2_2") (pintype "passive"))
    )
    (net (code "57") (name "UART3_RX") (class "Default")
      (node (ref "H1") (pin "52") (pinfunction "52_52") (pintype "passive"))
      (node (ref "J2") (pin "7") (pinfunction "7_7") (pintype "bidirectional"))
    )
    (net (code "58") (name "UART3_TX") (class "Default")
      (node (ref "H1") (pin "50") (pinfunction "50_50") (pintype "passive"))
      (node (ref "J2") (pin "8") (pinfunction "8_8") (pintype "bidirectional"))
    )
    (net (code "59") (name "UART8_RX") (class "Default")
      (node (ref "H1") (pin "3") (pinfunction "3_3") (pintype "passive"))
      (node (ref "J4") (pin "4") (pinfunction "4_4") (pintype "bidirectional"))
    )
    (net (code "60") (name "UART8_TX") (class "Default")
      (node (ref "H1") (pin "1") (pinfunction "1_1") (pintype "passive"))
      (node (ref "J4") (pin "3") (pinfunction "3_3") (pintype "bidirectional"))
    )
    (net (code "61") (name "unconnected-(ADC-A0-Pad7)") (class "Default")
      (node (ref "ADC") (pin "7") (pinfunction "A0_7") (pintype "input"))
    )
    (net (code "62") (name "unconnected-(ADC-A1-Pad8)") (class "Default")
      (node (ref "ADC") (pin "8") (pinfunction "A1_8") (pintype "input"))
    )
    (net (code "63") (name "unconnected-(ADC-IN5-Pad11)") (class "Default")
      (node (ref "ADC") (pin "11") (pinfunction "IN5_11") (pintype "input"))
    )
    (net (code "64") (name "unconnected-(ADC-IN6-Pad10)") (class "Default")
      (node (ref "ADC") (pin "10") (pinfunction "IN6_10") (pintype "input"))
    )
    (net (code "65") (name "unconnected-(ADC-IN7-Pad9)") (class "Default")
      (node (ref "ADC") (pin "9") (pinfunction "IN7_9") (pintype "input"))
    )
    (net (code "66") (name "unconnected-(ADC-INT-Pad6)") (class "Default")
      (node (ref "ADC") (pin "6") (pinfunction "INT_6") (pintype "output"))
    )
    (net (code "67") (name "unconnected-(H1-Pad6)") (class "Default")
      (node (ref "H1") (pin "6") (pinfunction "6_6") (pintype "passive"))
    )
    (net (code "68") (name "unconnected-(H1-Pad11)") (class "Default")
      (node (ref "H1") (pin "11") (pinfunction "11_11") (pintype "passive"))
    )
    (net (code "69") (name "unconnected-(H1-Pad13)") (class "Default")
      (node (ref "H1") (pin "13") (pinfunction "13_13") (pintype "passive"))
    )
    (net (code "70") (name "unconnected-(H1-Pad14)") (class "Default")
      (node (ref "H1") (pin "14") (pinfunction "14_14") (pintype "passive"))
    )
    (net (code "71") (name "unconnected-(H1-Pad15)") (class "Default")
      (node (ref "H1") (pin "15") (pinfunction "15_15") (pintype "passive"))
    )
    (net (code "72") (name "unconnected-(H1-Pad17)") (class "Default")
      (node (ref "H1") (pin "17") (pinfunction "17_17") (pintype "passive"))
    )
    (net (code "73") (name "unconnected-(H1-Pad23)") (class "Default")
      (node (ref "H1") (pin "23") (pinfunction "23_23") (pintype "passive"))
    )
    (net (code "74") (name "unconnected-(H1-Pad24)") (class "Default")
      (node (ref "H1") (pin "24") (pinfunction "24_24") (pintype "passive"))
    )
    (net (code "75") (name "unconnected-(H1-Pad25)") (class "Default")
      (node (ref "H1") (pin "25") (pinfunction "25_25") (pintype "passive"))
    )
    (net (code "76") (name "unconnected-(H1-Pad26)") (class "Default")
      (node (ref "H1") (pin "26") (pinfunction "26_26") (pintype "passive"))
    )
    (net (code "77") (name "unconnected-(H1-Pad27)") (class "Default")
      (node (ref "H1") (pin "27") (pinfunction "27_27") (pintype "passive"))
    )
    (net (code "78") (name "unconnected-(H1-Pad28)") (class "Default")
      (node (ref "H1") (pin "28") (pinfunction "28_28") (pintype "passive"))
    )
    (net (code "79") (name "unconnected-(H1-Pad29)") (class "Default")
      (node (ref "H1") (pin "29") (pinfunction "29_29") (pintype "passive"))
    )
    (net (code "80") (name "unconnected-(H1-Pad30)") (class "Default")
      (node (ref "H1") (pin "30") (pinfunction "30_30") (pintype "passive"))
    )
    (net (code "81") (name "unconnected-(H1-Pad31)") (class "Default")
      (node (ref "H1") (pin "31") (pinfunction "31_31") (pintype "passive"))
    )
    (net (code "82") (name "unconnected-(H1-Pad32)") (class "Default")
      (node (ref "H1") (pin "32") (pinfunction "32_32") (pintype "passive"))
    )
    (net (code "83") (name "unconnected-(H1-Pad33)") (class "Default")
      (node (ref "H1") (pin "33") (pinfunction "33_33") (pintype "passive"))
    )
    (net (code "84") (name "unconnected-(H1-Pad34)") (class "Default")
      (node (ref "H1") (pin "34") (pinfunction "34_34") (pintype "passive"))
    )
    (net (code "85") (name "unconnected-(H1-Pad39)") (class "Default")
      (node (ref "H1") (pin "39") (pinfunction "39_39") (pintype "passive"))
    )
    (net (code "86") (name "unconnected-(H1-Pad40)") (class "Default")
      (node (ref "H1") (pin "40") (pinfunction "40_40") (pintype "passive"))
    )
    (net (code "87") (name "unconnected-(H1-Pad41)") (class "Default")
      (node (ref "H1") (pin "41") (pinfunction "41_41") (pintype "passive"))
    )
    (net (code "88") (name "unconnected-(H1-Pad43)") (class "Default")
      (node (ref "H1") (pin "43") (pinfunction "43_43") (pintype "passive"))
    )
    (net (code "89") (name "unconnected-(H1-Pad45)") (class "Default")
      (node (ref "H1") (pin "45") (pinfunction "45_45") (pintype "passive"))
    )
    (net (code "90") (name "unconnected-(H1-Pad46)") (class "Default")
      (node (ref "H1") (pin "46") (pinfunction "46_46") (pintype "passive"))
    )
    (net (code "91") (name "unconnected-(H1-Pad47)") (class "Default")
      (node (ref "H1") (pin "47") (pinfunction "47_47") (pintype "passive"))
    )
    (net (code "92") (name "unconnected-(H1-Pad48)") (class "Default")
      (node (ref "H1") (pin "48") (pinfunction "48_48") (pintype "passive"))
    )
    (net (code "93") (name "unconnected-(H2-Pad1)") (class "Default")
      (node (ref "H2") (pin "1") (pinfunction "1_1") (pintype "passive"))
    )
    (net (code "94") (name "unconnected-(H2-Pad2)") (class "Default")
      (node (ref "H2") (pin "2") (pinfunction "2_2") (pintype "passive"))
    )
    (net (code "95") (name "unconnected-(H2-Pad3)") (class "Default")
      (node (ref "H2") (pin "3") (pinfunction "3_3") (pintype "passive"))
    )
    (net (code "96") (name "unconnected-(H2-Pad4)") (class "Default")
      (node (ref "H2") (pin "4") (pinfunction "4_4") (pintype "passive"))
    )
    (net (code "97") (name "unconnected-(H2-Pad5)") (class "Default")
      (node (ref "H2") (pin "5") (pinfunction "5_5") (pintype "passive"))
    )
    (net (code "98") (name "unconnected-(H2-Pad6)") (class "Default")
      (node (ref "H2") (pin "6") (pinfunction "6_6") (pintype "passive"))
    )
    (net (code "99") (name "unconnected-(H2-Pad7)") (class "Default")
      (node (ref "H2") (pin "7") (pinfunction "7_7") (pintype "passive"))
    )
    (net (code "100") (name "unconnected-(H2-Pad8)") (class "Default")
      (node (ref "H2") (pin "8") (pinfunction "8_8") (pintype "passive"))
    )
    (net (code "101") (name "unconnected-(H2-Pad9)") (class "Default")
      (node (ref "H2") (pin "9") (pinfunction "9_9") (pintype "passive"))
    )
    (net (code "102") (name "unconnected-(H2-Pad11)") (class "Default")
      (node (ref "H2") (pin "11") (pinfunction "11_11") (pintype "passive"))
    )
    (net (code "103") (name "unconnected-(H2-Pad12)") (class "Default")
      (node (ref "H2") (pin "12") (pinfunction "12_12") (pintype "passive"))
    )
    (net (code "104") (name "unconnected-(H2-Pad23)") (class "Default")
      (node (ref "H2") (pin "23") (pinfunction "23_23") (pintype "passive"))
    )
    (net (code "105") (name "unconnected-(H2-Pad24)") (class "Default")
      (node (ref "H2") (pin "24") (pinfunction "24_24") (pintype "passive"))
    )
    (net (code "106") (name "unconnected-(H2-Pad32)") (class "Default")
      (node (ref "H2") (pin "32") (pinfunction "32_32") (pintype "passive"))
    )
    (net (code "107") (name "unconnected-(H2-Pad33)") (class "Default")
      (node (ref "H2") (pin "33") (pinfunction "33_33") (pintype "passive"))
    )
    (net (code "108") (name "unconnected-(H2-Pad34)") (class "Default")
      (node (ref "H2") (pin "34") (pinfunction "34_34") (pintype "passive"))
    )
    (net (code "109") (name "unconnected-(H2-Pad35)") (class "Default")
      (node (ref "H2") (pin "35") (pinfunction "35_35") (pintype "passive"))
    )
    (net (code "110") (name "unconnected-(H2-Pad36)") (class "Default")
      (node (ref "H2") (pin "36") (pinfunction "36_36") (pintype "passive"))
    )
    (net (code "111") (name "unconnected-(H2-Pad37)") (class "Default")
      (node (ref "H2") (pin "37") (pinfunction "37_37") (pintype "passive"))
    )
    (net (code "112") (name "unconnected-(H2-Pad38)") (class "Default")
      (node (ref "H2") (pin "38") (pinfunction "38_38") (pintype "passive"))
    )
    (net (code "113") (name "unconnected-(H2-Pad39)") (class "Default")
      (node (ref "H2") (pin "39") (pinfunction "39_39") (pintype "passive"))
    )
    (net (code "114") (name "unconnected-(H2-Pad40)") (class "Default")
      (node (ref "H2") (pin "40") (pinfunction "40_40") (pintype "passive"))
    )
    (net (code "115") (name "unconnected-(H2-Pad41)") (class "Default")
      (node (ref "H2") (pin "41") (pinfunction "41_41") (pintype "passive"))
    )
    (net (code "116") (name "unconnected-(H2-Pad42)") (class "Default")
      (node (ref "H2") (pin "42") (pinfunction "42_42") (pintype "passive"))
    )
    (net (code "117") (name "unconnected-(H2-Pad43)") (class "Default")
      (node (ref "H2") (pin "43") (pinfunction "43_43") (pintype "passive"))
    )
    (net (code "118") (name "unconnected-(H2-Pad44)") (class "Default")
      (node (ref "H2") (pin "44") (pinfunction "44_44") (pintype "passive"))
    )
    (net (code "119") (name "unconnected-(H2-Pad45)") (class "Default")
      (node (ref "H2") (pin "45") (pinfunction "45_45") (pintype "passive"))
    )
    (net (code "120") (name "unconnected-(H2-Pad46)") (class "Default")
      (node (ref "H2") (pin "46") (pinfunction "46_46") (pintype "passive"))
    )
    (net (code "121") (name "unconnected-(H2-Pad50)") (class "Default")
      (node (ref "H2") (pin "50") (pinfunction "50_50") (pintype "passive"))
    )
    (net (code "122") (name "unconnected-(H2-Pad51)") (class "Default")
      (node (ref "H2") (pin "51") (pinfunction "51_51") (pintype "passive"))
    )
    (net (code "123") (name "unconnected-(H2-Pad52)") (class "Default")
      (node (ref "H2") (pin "52") (pinfunction "52_52") (pintype "passive"))
    )
    (net (code "124") (name "unconnected-(IC2-DRDY-Pad9)") (class "Default")
      (node (ref "IC2") (pin "9") (pinfunction "DRDY_9") (pintype "bidirectional"))
    )
    (net (code "125") (name "unconnected-(IC2-INT1-Pad5)") (class "Default")
      (node (ref "IC2") (pin "5") (pinfunction "INT1_5") (pintype "bidirectional"))
    )
    (net (code "126") (name "unconnected-(IC2-INT2-Pad4)") (class "Default")
      (node (ref "IC2") (pin "4") (pinfunction "INT2_4") (pintype "bidirectional"))
    )
    (net (code "127") (name "unconnected-(IC3-DRDY-Pad9)") (class "Default")
      (node (ref "IC3") (pin "9") (pinfunction "DRDY_9") (pintype "bidirectional"))
    )
    (net (code "128") (name "unconnected-(IC3-INT1-Pad5)") (class "Default")
      (node (ref "IC3") (pin "5") (pinfunction "INT1_5") (pintype "bidirectional"))
    )
    (net (code "129") (name "unconnected-(IC3-INT2-Pad4)") (class "Default")
      (node (ref "IC3") (pin "4") (pinfunction "INT2_4") (pintype "bidirectional"))
    )
    (net (code "130") (name "unconnected-(IC6-DRDY-Pad9)") (class "Default")
      (node (ref "IC6") (pin "9") (pinfunction "DRDY_9") (pintype "bidirectional"))
    )
    (net (code "131") (name "unconnected-(IC6-INT1-Pad5)") (class "Default")
      (node (ref "IC6") (pin "5") (pinfunction "INT1_5") (pintype "bidirectional"))
    )
    (net (code "132") (name "unconnected-(IC6-INT2-Pad4)") (class "Default")
      (node (ref "IC6") (pin "4") (pinfunction "INT2_4") (pintype "bidirectional"))
    )
    (net (code "133") (name "unconnected-(J2-Pad6)") (class "Default")
      (node (ref "J2") (pin "6") (pinfunction "6_6") (pintype "bidirectional"))
    )
    (net (code "134") (name "unconnected-(J2-Pad9)") (class "Default")
      (node (ref "J2") (pin "9") (pinfunction "9_9") (pintype "bidirectional"))
    )
    (net (code "135") (name "unconnected-(J2-Pad10)") (class "Default")
      (node (ref "J2") (pin "10") (pinfunction "10_10") (pintype "bidirectional"))
    )
    (net (code "136") (name "unconnected-(J2-PadMP1)") (class "Default")
      (node (ref "J2") (pin "MP1") (pinfunction "MP1_MP1") (pintype "bidirectional"))
    )
    (net (code "137") (name "unconnected-(J2-PadMP2)") (class "Default")
      (node (ref "J2") (pin "MP2") (pinfunction "MP2_MP2") (pintype "bidirectional"))
    )
    (net (code "138") (name "unconnected-(J4-Pad9)") (class "Default")
      (node (ref "J4") (pin "9") (pinfunction "9_9") (pintype "bidirectional"))
    )
    (net (code "139") (name "unconnected-(J4-Pad10)") (class "Default")
      (node (ref "J4") (pin "10") (pinfunction "10_10") (pintype "bidirectional"))
    )
    (net (code "140") (name "unconnected-(J7-PadMP1)") (class "Default")
      (node (ref "J7") (pin "MP1") (pinfunction "MP1_MP1") (pintype "bidirectional"))
    )
    (net (code "141") (name "unconnected-(J7-PadMP2)") (class "Default")
      (node (ref "J7") (pin "MP2") (pinfunction "MP2_MP2") (pintype "bidirectional"))
    )
    (net (code "142") (name "unconnected-(J8-PadMP1)") (class "Default")
      (node (ref "J8") (pin "MP1") (pinfunction "MP1_MP1") (pintype "bidirectional"))
    )
    (net (code "143") (name "unconnected-(J8-PadMP2)") (class "Default")
      (node (ref "J8") (pin "MP2") (pinfunction "MP2_MP2") (pintype "bidirectional"))
    )
    (net (code "144") (name "unconnected-(J9-PadMP1)") (class "Default")
      (node (ref "J9") (pin "MP1") (pinfunction "MP1_MP1") (pintype "bidirectional"))
    )
    (net (code "145") (name "unconnected-(J9-PadMP2)") (class "Default")
      (node (ref "J9") (pin "MP2") (pinfunction "MP2_MP2") (pintype "bidirectional"))
    )
    (net (code "146") (name "unconnected-(J10-PadMP1)") (class "Default")
      (node (ref "J10") (pin "MP1") (pinfunction "MP1_MP1") (pintype "bidirectional"))
    )
    (net (code "147") (name "unconnected-(J10-PadMP2)") (class "Default")
      (node (ref "J10") (pin "MP2") (pinfunction "MP2_MP2") (pintype "bidirectional"))
    )
    (net (code "148") (name "unconnected-(U1-INT1-Pad3)") (class "Default")
      (node (ref "U1") (pin "3") (pinfunction "INT1_3") (pintype "output"))
    )
    (net (code "149") (name "unconnected-(U1-INT2{slash}PWR_CTRL-Pad2)") (class "Default")
      (node (ref "U1") (pin "2") (pinfunction "INT2/PWR_CTRL_2") (pintype "bidirectional"))
    )
    (net (code "150") (name "unconnected-(U3-SQW-Pad7)") (class "Default")
      (node (ref "U3") (pin "7") (pinfunction "SQW_7") (pintype "output"))
    )
    (net (code "151") (name "unconnected-(U4-INT1-Pad3)") (class "Default")
      (node (ref "U4") (pin "3") (pinfunction "INT1_3") (pintype "output"))
    )
    (net (code "152") (name "unconnected-(U4-INT2{slash}PWR_CTRL-Pad2)") (class "Default")
      (node (ref "U4") (pin "2") (pinfunction "INT2/PWR_CTRL_2") (pintype "bidirectional"))
    )
    (net (code "153") (name "unconnected-(U6-INT1-Pad3)") (class "Default")
      (node (ref "U6") (pin "3") (pinfunction "INT1_3") (pintype "output"))
    )
    (net (code "154") (name "unconnected-(U6-INT2{slash}PWR_CTRL-Pad2)") (class "Default")
      (node (ref "U6") (pin "2") (pinfunction "INT2/PWR_CTRL_2") (pintype "bidirectional"))
    )
  )
)
